# TK90X.net
KiCad netlist of a schematic drawn in EAGLE
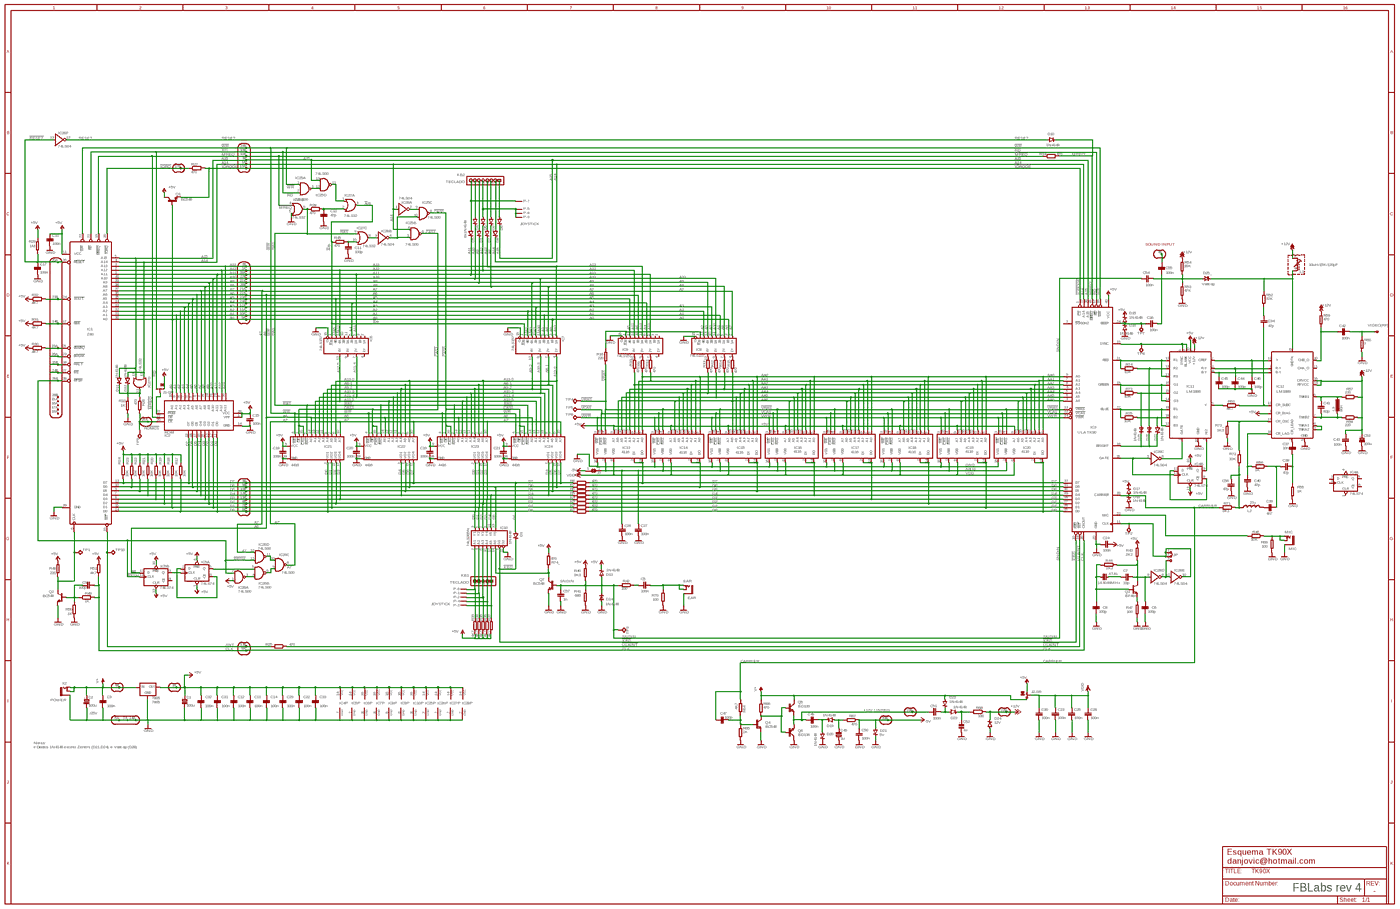
[diagram p0: schematic, sheet 1, overview]
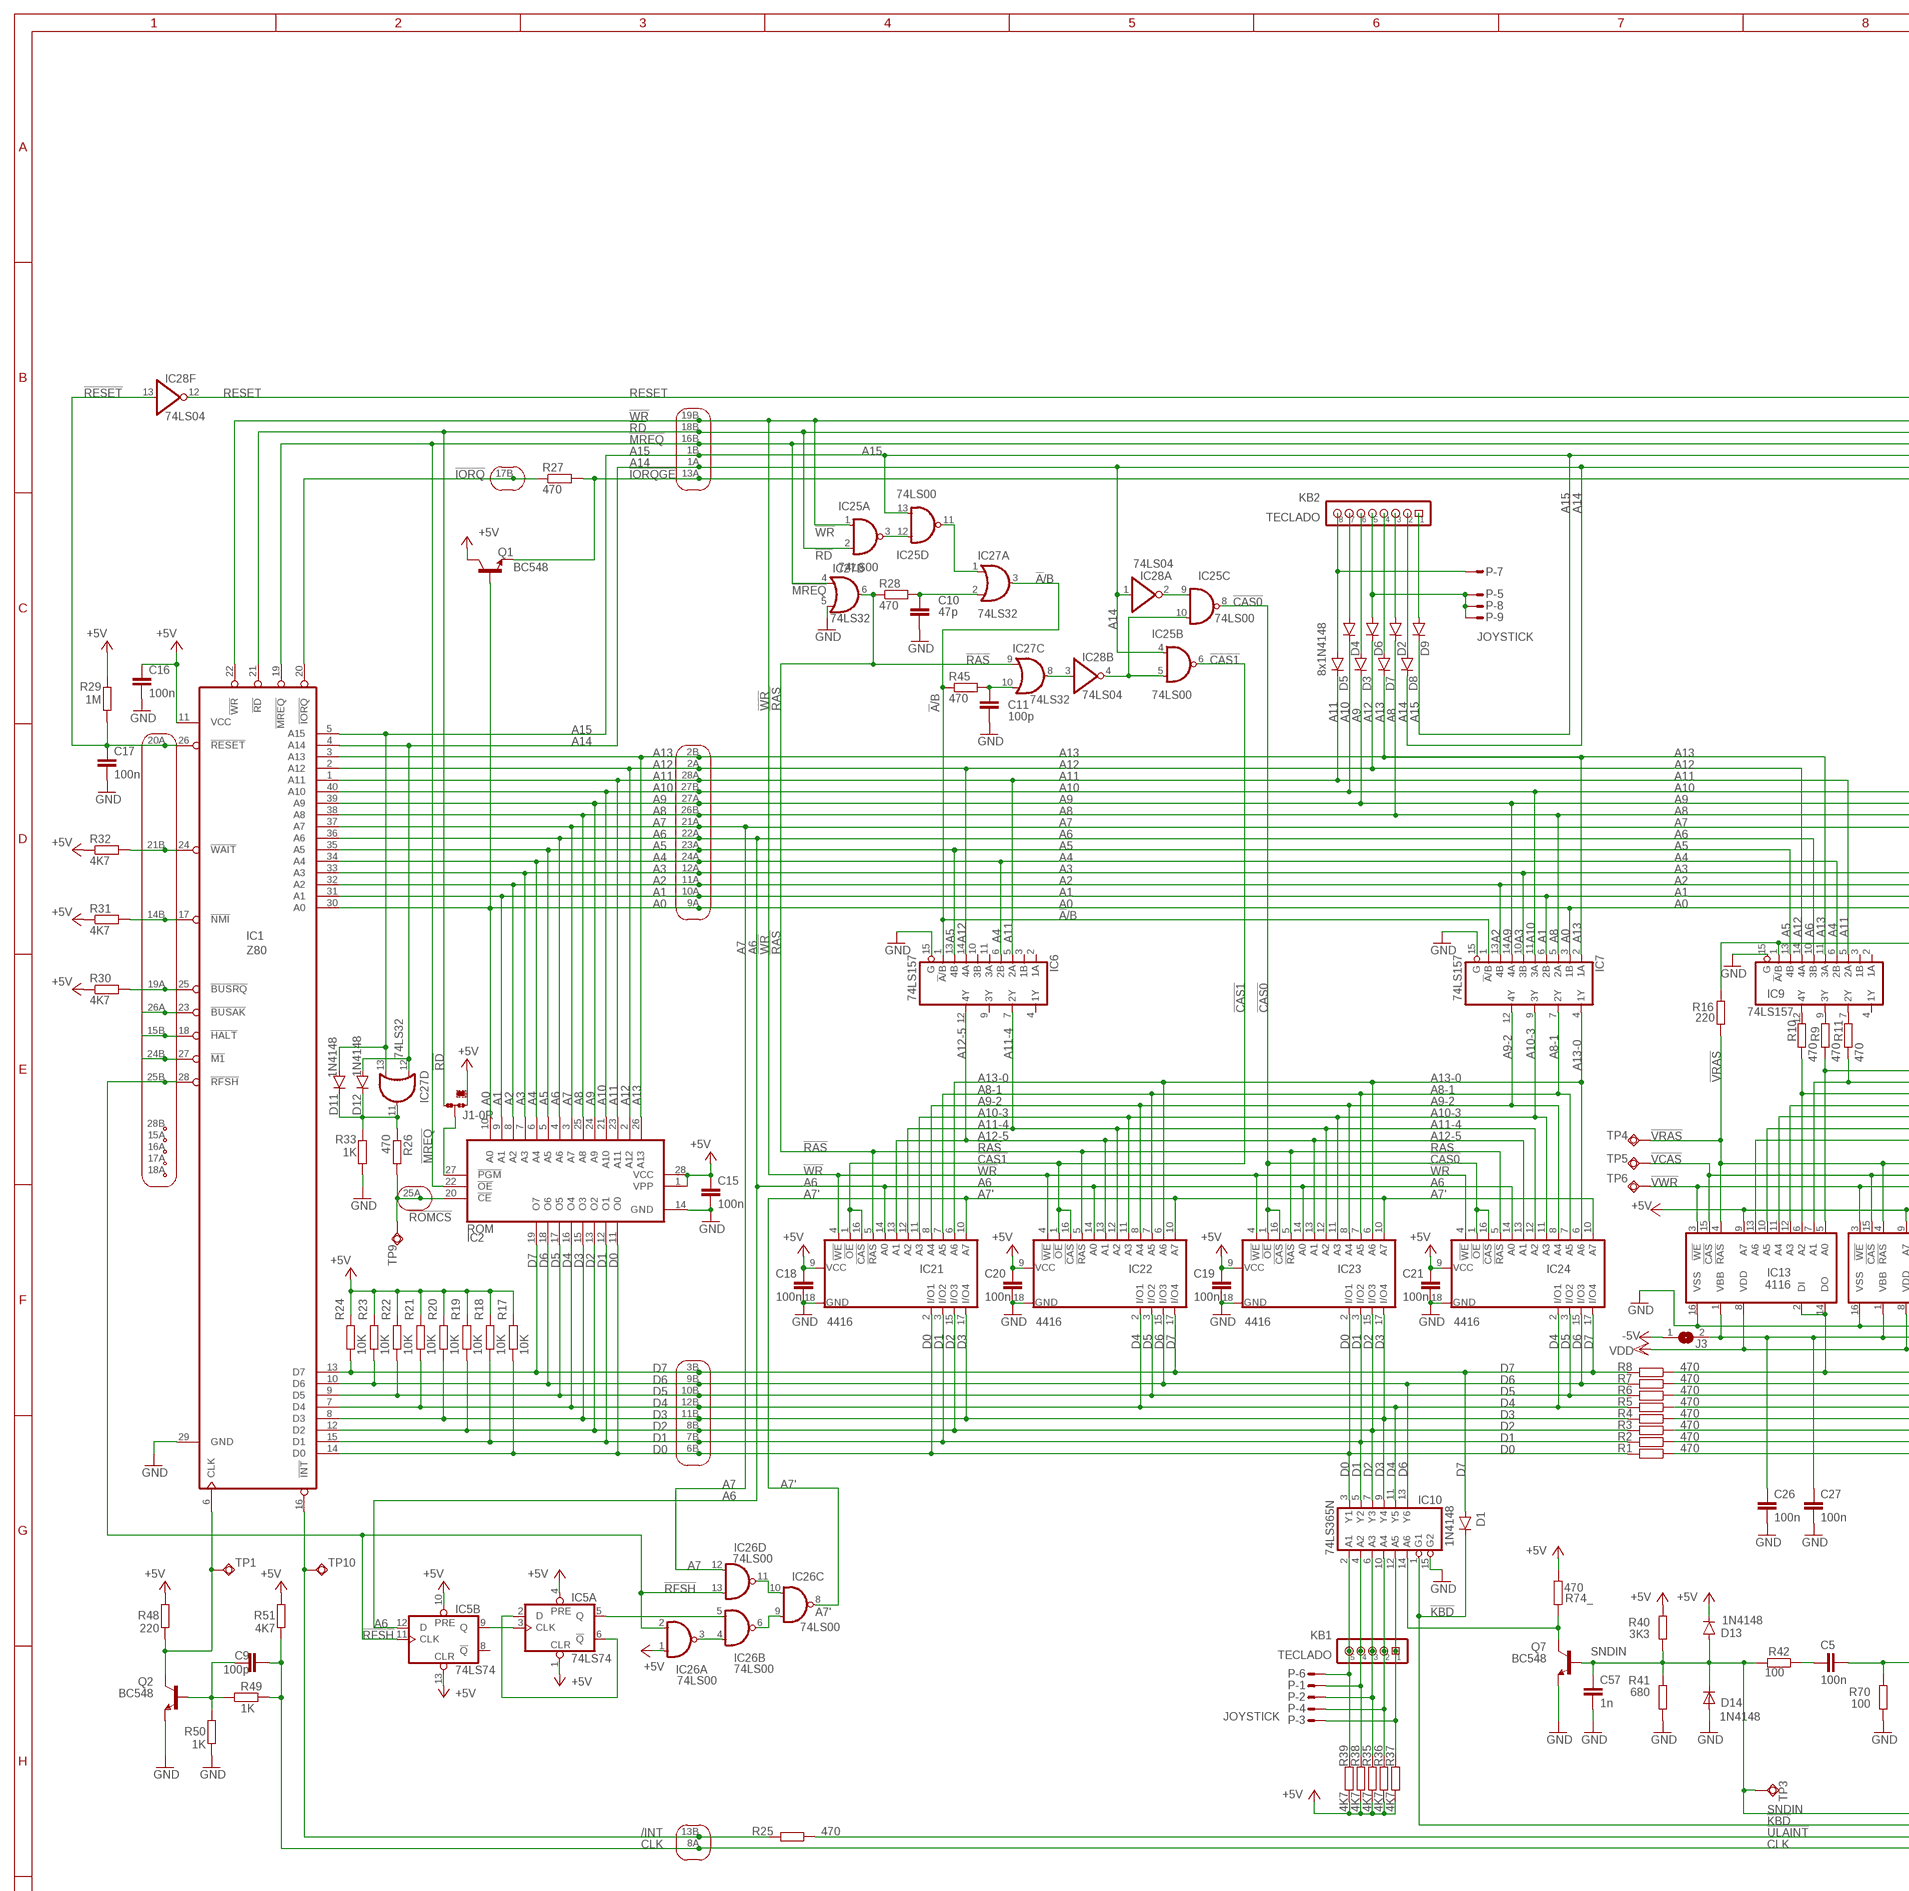
[diagram p1: schematic, sheet 1, part 1 of 4]
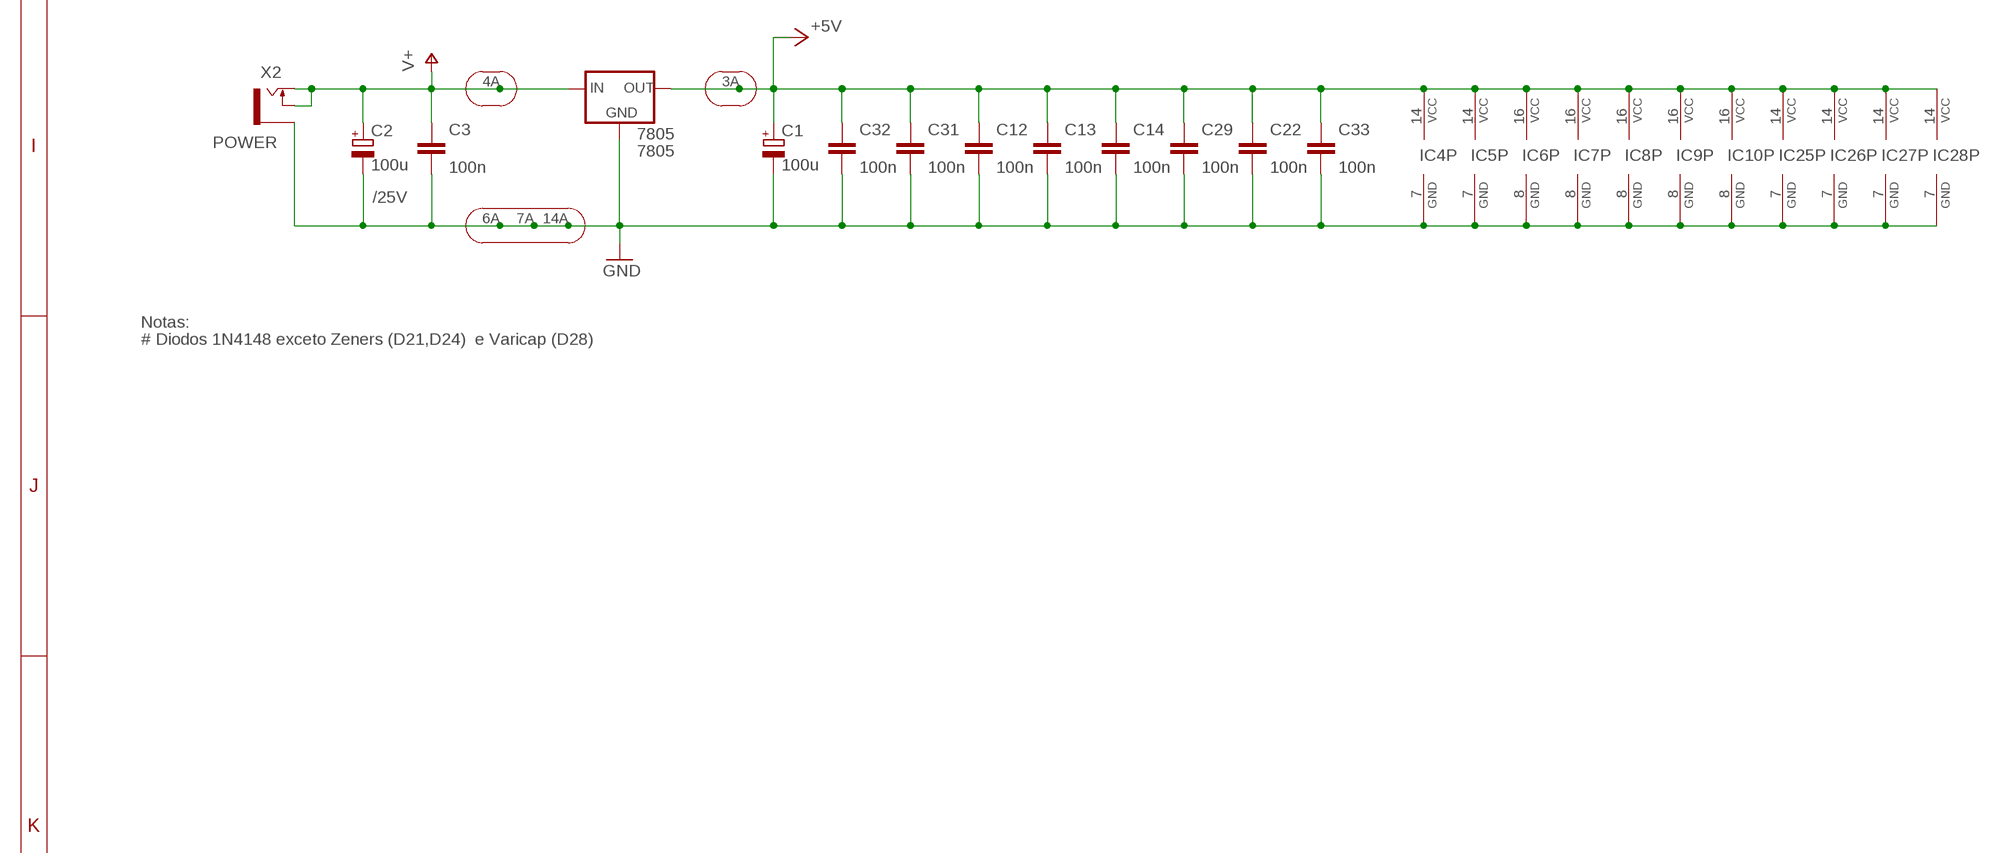
[diagram p2: schematic, sheet 1, part 2 of 4]
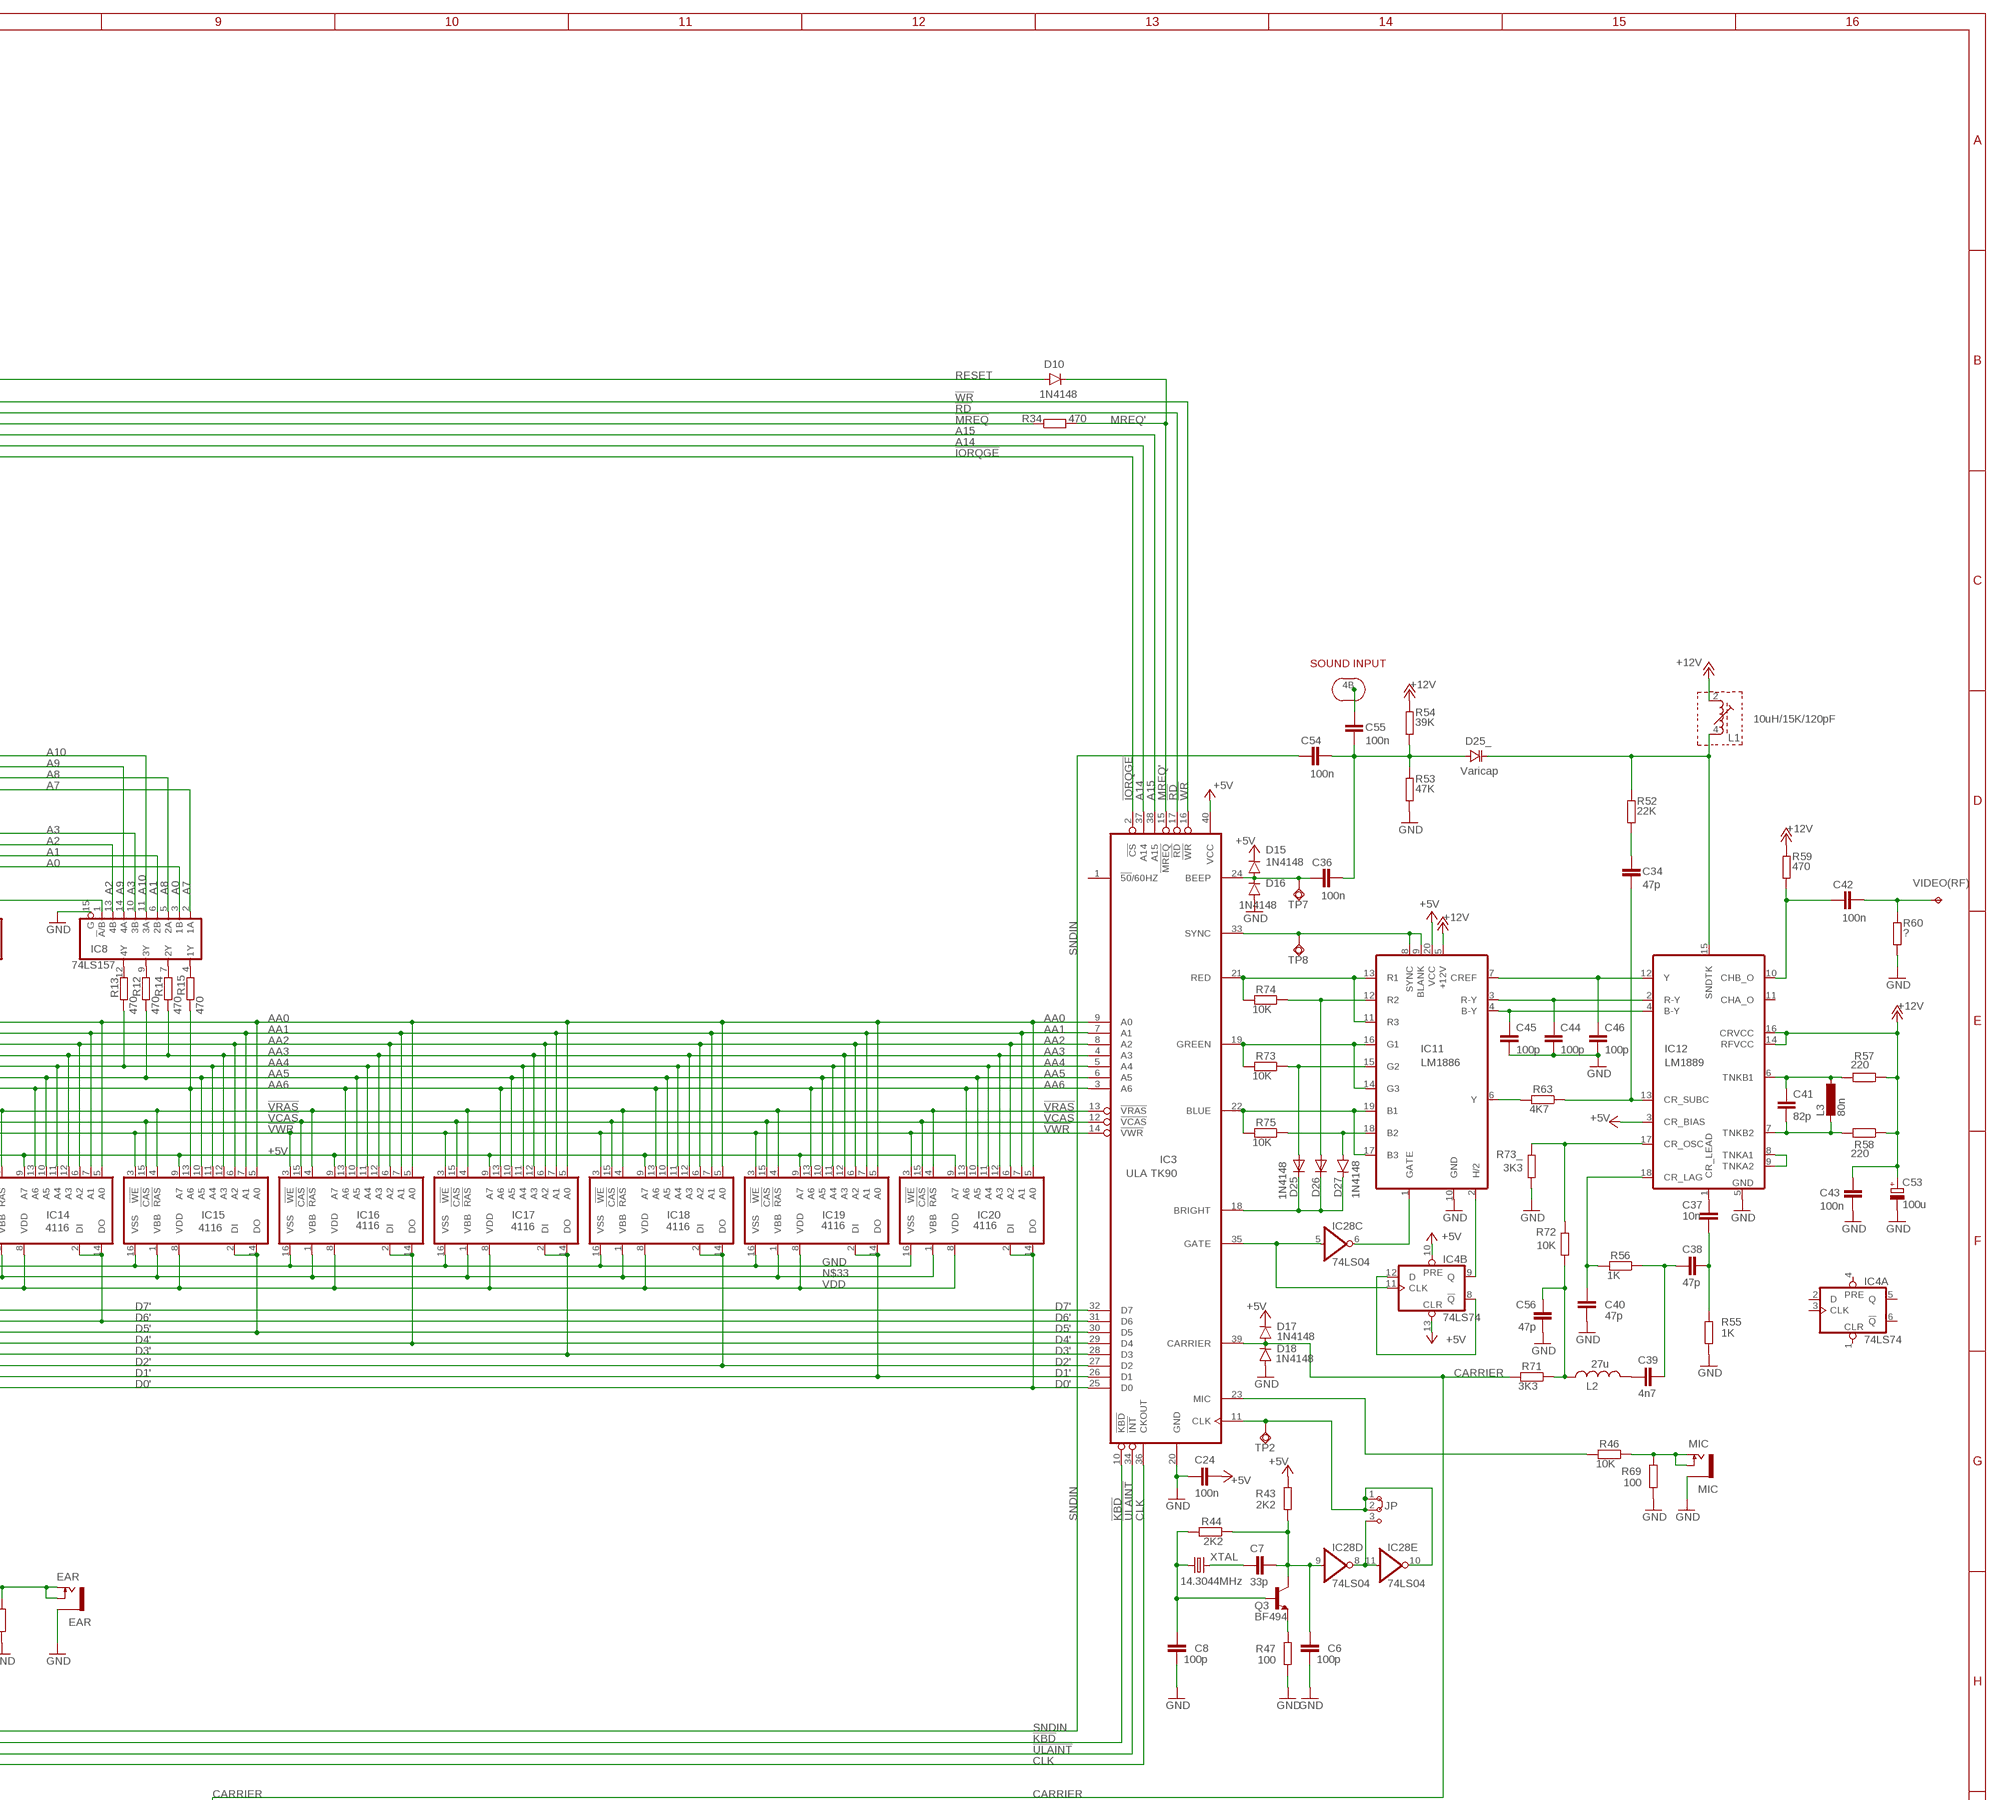
[diagram p3: schematic, sheet 1, part 3 of 4]
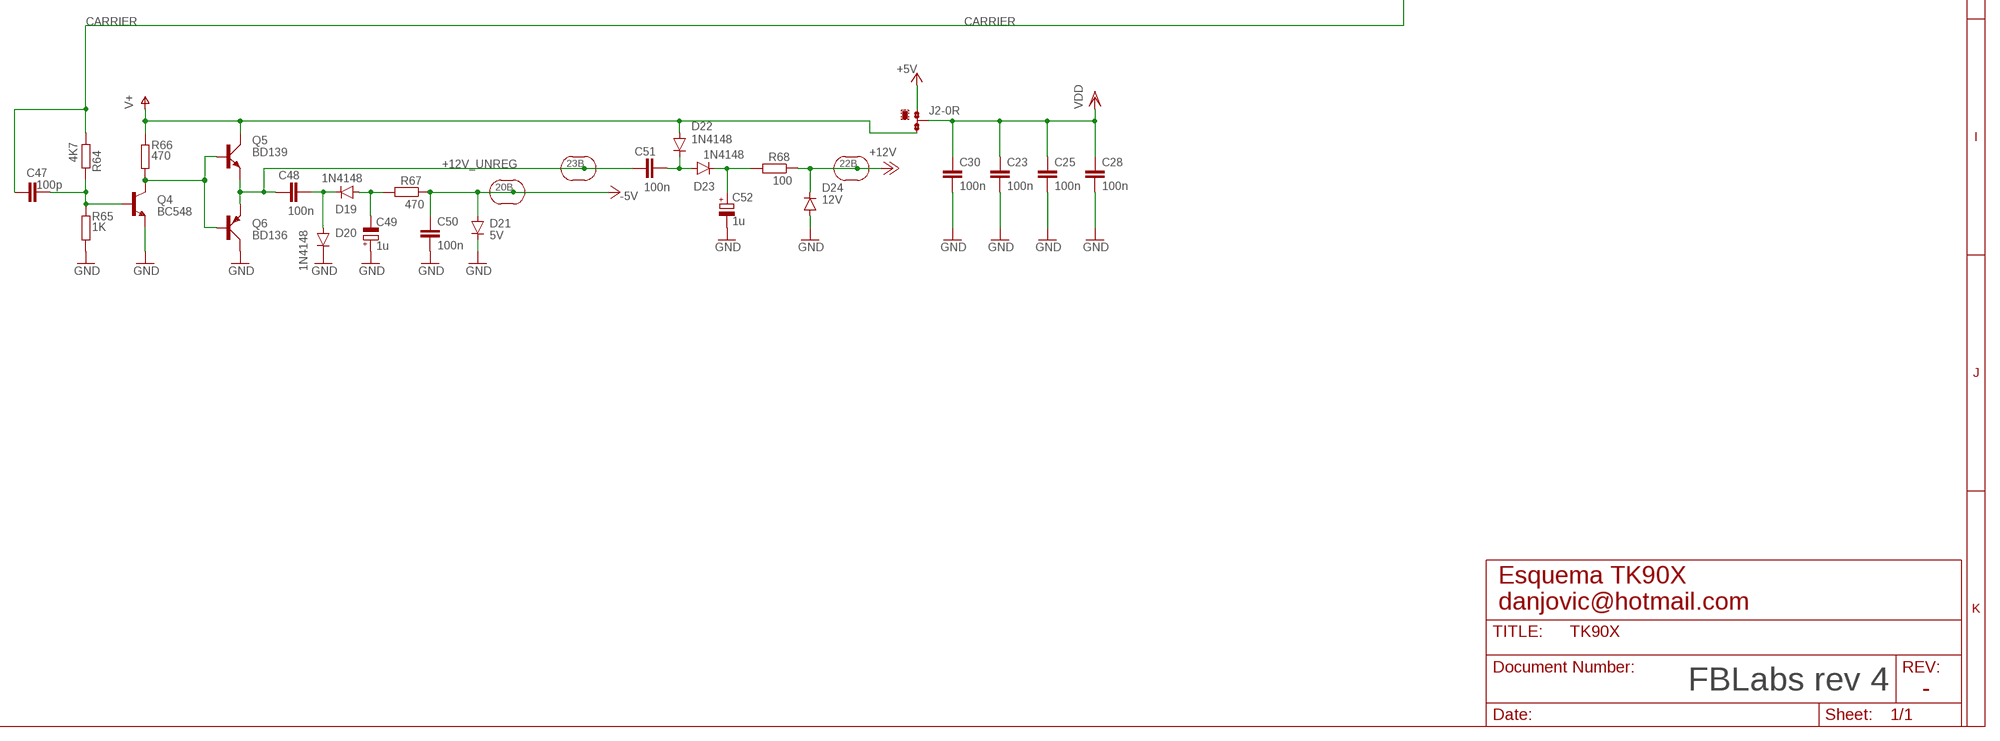
[diagram p4: schematic, sheet 1, part 4 of 4]

(export (version "E")
  (design (tool "Eeschema 10.0.6"))
  (components
    (comp (ref "7805")
      (value "7805")
      (footprint "eagle-import:78XXL")
      (libsource (lib "eagle-import") (part "78XXL"))
    )
    (comp (ref "C1")
      (value "100u")
      (footprint "eagle-import:E5-8,5")
      (libsource (lib "eagle-import") (part "CPOL-EUE5-8.5"))
    )
    (comp (ref "C2")
      (value "100u")
      (footprint "eagle-import:E5-8,5")
      (libsource (lib "eagle-import") (part "CPOL-EUE5-8.5"))
    )
    (comp (ref "C3")
      (value "100n")
      (footprint "eagle-import:C050-024X044")
      (libsource (lib "eagle-import") (part "C-EU050-024X044"))
    )
    (comp (ref "C5")
      (value "100n")
      (footprint "eagle-import:C050-024X044")
      (libsource (lib "eagle-import") (part "C-EU050-024X044"))
    )
    (comp (ref "C6")
      (value "100p")
      (footprint "eagle-import:C050-024X044")
      (libsource (lib "eagle-import") (part "C-EU050-024X044"))
    )
    (comp (ref "C7")
      (value "33p")
      (footprint "eagle-import:C050-024X044")
      (libsource (lib "eagle-import") (part "C-EU050-024X044"))
    )
    (comp (ref "C8")
      (value "100p")
      (footprint "eagle-import:C050-024X044")
      (libsource (lib "eagle-import") (part "C-EU050-024X044"))
    )
    (comp (ref "C9")
      (value "100p")
      (footprint "eagle-import:C050-024X044")
      (libsource (lib "eagle-import") (part "C-EU050-024X044"))
    )
    (comp (ref "C10")
      (value "47p")
      (footprint "eagle-import:C050-024X044")
      (libsource (lib "eagle-import") (part "C-EU050-024X044"))
    )
    (comp (ref "C11")
      (value "100p")
      (footprint "eagle-import:C050-024X044")
      (libsource (lib "eagle-import") (part "C-EU050-024X044"))
    )
    (comp (ref "C12")
      (value "100n")
      (footprint "eagle-import:C050-024X044")
      (libsource (lib "eagle-import") (part "C-EU050-024X044"))
    )
    (comp (ref "C13")
      (value "100n")
      (footprint "eagle-import:C050-024X044")
      (libsource (lib "eagle-import") (part "C-EU050-024X044"))
    )
    (comp (ref "C14")
      (value "100n")
      (footprint "eagle-import:C050-024X044")
      (libsource (lib "eagle-import") (part "C-EU050-024X044"))
    )
    (comp (ref "C15")
      (value "100n")
      (footprint "eagle-import:C050-024X044")
      (libsource (lib "eagle-import") (part "C-EU050-024X044"))
    )
    (comp (ref "C16")
      (value "100n")
      (footprint "eagle-import:C050-024X044")
      (libsource (lib "eagle-import") (part "C-EU050-024X044"))
    )
    (comp (ref "C17")
      (value "100n")
      (footprint "eagle-import:C050-024X044")
      (libsource (lib "eagle-import") (part "C-EU050-024X044"))
    )
    (comp (ref "C18")
      (value "100n")
      (footprint "eagle-import:C050-024X044")
      (libsource (lib "eagle-import") (part "C-EU050-024X044"))
    )
    (comp (ref "C19")
      (value "100n")
      (footprint "eagle-import:C050-024X044")
      (libsource (lib "eagle-import") (part "C-EU050-024X044"))
    )
    (comp (ref "C20")
      (value "100n")
      (footprint "eagle-import:C050-024X044")
      (libsource (lib "eagle-import") (part "C-EU050-024X044"))
    )
    (comp (ref "C21")
      (value "100n")
      (footprint "eagle-import:C050-024X044")
      (libsource (lib "eagle-import") (part "C-EU050-024X044"))
    )
    (comp (ref "C22")
      (value "100n")
      (footprint "eagle-import:C050-024X044")
      (libsource (lib "eagle-import") (part "C-EU050-024X044"))
    )
    (comp (ref "C23")
      (value "100n")
      (footprint "eagle-import:C050-024X044")
      (libsource (lib "eagle-import") (part "C-EU050-024X044"))
    )
    (comp (ref "C24")
      (value "100n")
      (footprint "eagle-import:C050-024X044")
      (libsource (lib "eagle-import") (part "C-EU050-024X044"))
    )
    (comp (ref "C25")
      (value "100n")
      (footprint "eagle-import:C050-024X044")
      (libsource (lib "eagle-import") (part "C-EU050-024X044"))
    )
    (comp (ref "C26")
      (value "100n")
      (footprint "eagle-import:C050-024X044")
      (libsource (lib "eagle-import") (part "C-EU050-024X044"))
    )
    (comp (ref "C27")
      (value "100n")
      (footprint "eagle-import:C050-024X044")
      (libsource (lib "eagle-import") (part "C-EU050-024X044"))
    )
    (comp (ref "C28")
      (value "100n")
      (footprint "eagle-import:C050-024X044")
      (libsource (lib "eagle-import") (part "C-EU050-024X044"))
    )
    (comp (ref "C29")
      (value "100n")
      (footprint "eagle-import:C050-024X044")
      (libsource (lib "eagle-import") (part "C-EU050-024X044"))
    )
    (comp (ref "C30")
      (value "100n")
      (footprint "eagle-import:C050-024X044")
      (libsource (lib "eagle-import") (part "C-EU050-024X044"))
    )
    (comp (ref "C31")
      (value "100n")
      (footprint "eagle-import:C050-024X044")
      (libsource (lib "eagle-import") (part "C-EU050-024X044"))
    )
    (comp (ref "C32")
      (value "100n")
      (footprint "eagle-import:C050-024X044")
      (libsource (lib "eagle-import") (part "C-EU050-024X044"))
    )
    (comp (ref "C33")
      (value "100n")
      (footprint "eagle-import:C050-024X044")
      (libsource (lib "eagle-import") (part "C-EU050-024X044"))
    )
    (comp (ref "C34")
      (value "47p")
      (footprint "eagle-import:C050-024X044")
      (libsource (lib "eagle-import") (part "C-EU050-024X044"))
    )
    (comp (ref "C36")
      (value "100n")
      (footprint "eagle-import:C050-024X044")
      (libsource (lib "eagle-import") (part "C-EU050-024X044"))
    )
    (comp (ref "C37")
      (value "10n")
      (footprint "eagle-import:C050-024X044")
      (libsource (lib "eagle-import") (part "C-EU050-024X044"))
    )
    (comp (ref "C38")
      (value "47p")
      (footprint "eagle-import:C050-024X044")
      (libsource (lib "eagle-import") (part "C-EU050-024X044"))
    )
    (comp (ref "C39")
      (value "4n7")
      (footprint "eagle-import:C050-024X044")
      (libsource (lib "eagle-import") (part "C-EU050-024X044"))
    )
    (comp (ref "C40")
      (value "47p")
      (footprint "eagle-import:C050-024X044")
      (libsource (lib "eagle-import") (part "C-EU050-024X044"))
    )
    (comp (ref "C41")
      (value "82p")
      (footprint "eagle-import:C050-024X044")
      (libsource (lib "eagle-import") (part "C-EU050-024X044"))
    )
    (comp (ref "C42")
      (value "100n")
      (footprint "eagle-import:C050-024X044")
      (libsource (lib "eagle-import") (part "C-EU050-024X044"))
    )
    (comp (ref "C43")
      (value "100n")
      (footprint "eagle-import:C050-024X044")
      (libsource (lib "eagle-import") (part "C-EU050-024X044"))
    )
    (comp (ref "C44")
      (value "100p")
      (footprint "eagle-import:C050-024X044")
      (libsource (lib "eagle-import") (part "C-EU050-024X044"))
    )
    (comp (ref "C45")
      (value "100p")
      (footprint "eagle-import:C050-024X044")
      (libsource (lib "eagle-import") (part "C-EU050-024X044"))
    )
    (comp (ref "C46")
      (value "100p")
      (footprint "eagle-import:C050-024X044")
      (libsource (lib "eagle-import") (part "C-EU050-024X044"))
    )
    (comp (ref "C47")
      (value "100p")
      (footprint "eagle-import:C050-024X044")
      (libsource (lib "eagle-import") (part "C-EU050-024X044"))
    )
    (comp (ref "C48")
      (value "100n")
      (footprint "eagle-import:C050-024X044")
      (libsource (lib "eagle-import") (part "C-EU050-024X044"))
    )
    (comp (ref "C49")
      (value "1u")
      (footprint "eagle-import:E2-4")
      (libsource (lib "eagle-import") (part "CPOL-EUE2-4"))
    )
    (comp (ref "C50")
      (value "100n")
      (footprint "eagle-import:C050-024X044")
      (libsource (lib "eagle-import") (part "C-EU050-024X044"))
    )
    (comp (ref "C51")
      (value "100n")
      (footprint "eagle-import:C050-024X044")
      (libsource (lib "eagle-import") (part "C-EU050-024X044"))
    )
    (comp (ref "C52")
      (value "1u")
      (footprint "eagle-import:E2-5")
      (libsource (lib "eagle-import") (part "CPOL-EUE2-5"))
    )
    (comp (ref "C53")
      (value "100u")
      (footprint "eagle-import:E5-4")
      (libsource (lib "eagle-import") (part "CPOL-EUE5-4"))
    )
    (comp (ref "C54")
      (value "100n")
      (footprint "eagle-import:C050-024X044")
      (libsource (lib "eagle-import") (part "C-EU050-024X044"))
    )
    (comp (ref "C55")
      (value "100n")
      (footprint "eagle-import:C050-024X044")
      (libsource (lib "eagle-import") (part "C-EU050-024X044"))
    )
    (comp (ref "C56")
      (value "47p")
      (footprint "eagle-import:C050-024X044")
      (libsource (lib "eagle-import") (part "C-EU050-024X044"))
    )
    (comp (ref "C57")
      (value "1n")
      (footprint "eagle-import:C050-024X044")
      (libsource (lib "eagle-import") (part "C-EU050-024X044"))
    )
    (comp (ref "D1")
      (value "1N4148")
      (footprint "eagle-import:DO35-12")
      (libsource (lib "eagle-import") (part "DDO35-12"))
    )
    (comp (ref "D2")
      (value "1N4148")
      (footprint "eagle-import:DO35-12")
      (libsource (lib "eagle-import") (part "DDO35-12"))
    )
    (comp (ref "D3")
      (value "1N4148")
      (footprint "eagle-import:DO35-12")
      (libsource (lib "eagle-import") (part "DDO35-12"))
    )
    (comp (ref "D4")
      (value "1N4148")
      (footprint "eagle-import:DO35-12")
      (libsource (lib "eagle-import") (part "DDO35-12"))
    )
    (comp (ref "D5")
      (value "1N4148")
      (footprint "eagle-import:DO35-12")
      (libsource (lib "eagle-import") (part "DDO35-12"))
    )
    (comp (ref "D6")
      (value "1N4148")
      (footprint "eagle-import:DO35-12")
      (libsource (lib "eagle-import") (part "DDO35-12"))
    )
    (comp (ref "D7")
      (value "1N4148")
      (footprint "eagle-import:DO35-12")
      (libsource (lib "eagle-import") (part "DDO35-12"))
    )
    (comp (ref "D8")
      (value "1N4148")
      (footprint "eagle-import:DO35-12")
      (libsource (lib "eagle-import") (part "DDO35-12"))
    )
    (comp (ref "D9")
      (value "1N4148")
      (footprint "eagle-import:DO35-12")
      (libsource (lib "eagle-import") (part "DDO35-12"))
    )
    (comp (ref "D10")
      (value "1N4148")
      (footprint "eagle-import:DO35-12")
      (libsource (lib "eagle-import") (part "DDO35-12"))
    )
    (comp (ref "D11")
      (value "1N4148")
      (footprint "eagle-import:DO35-12")
      (libsource (lib "eagle-import") (part "DDO35-12"))
    )
    (comp (ref "D12")
      (value "1N4148")
      (footprint "eagle-import:DO35-12")
      (libsource (lib "eagle-import") (part "DDO35-12"))
    )
    (comp (ref "D13")
      (value "1N4148")
      (footprint "eagle-import:DO35-12")
      (libsource (lib "eagle-import") (part "DDO35-12"))
    )
    (comp (ref "D14")
      (value "1N4148")
      (footprint "eagle-import:D-5")
      (libsource (lib "eagle-import") (part "DIODE-D-5"))
    )
    (comp (ref "D15")
      (value "1N4148")
      (footprint "eagle-import:DO35-12")
      (libsource (lib "eagle-import") (part "DDO35-12"))
    )
    (comp (ref "D16")
      (value "1N4148")
      (footprint "eagle-import:DO35-12")
      (libsource (lib "eagle-import") (part "DDO35-12"))
    )
    (comp (ref "D17")
      (value "1N4148")
      (footprint "eagle-import:DO35-12")
      (libsource (lib "eagle-import") (part "DDO35-12"))
    )
    (comp (ref "D18")
      (value "1N4148")
      (footprint "eagle-import:DO35-12")
      (libsource (lib "eagle-import") (part "DDO35-12"))
    )
    (comp (ref "D19")
      (value "1N4148")
      (footprint "eagle-import:DO35-12")
      (libsource (lib "eagle-import") (part "DDO35-12"))
    )
    (comp (ref "D20")
      (value "1N4148")
      (footprint "eagle-import:DO35-12")
      (libsource (lib "eagle-import") (part "DDO35-12"))
    )
    (comp (ref "D21")
      (value "5V")
      (footprint "eagle-import:DO35-12")
      (libsource (lib "eagle-import") (part "DDO35-12"))
    )
    (comp (ref "D22")
      (value "1N4148")
      (footprint "eagle-import:DO35-12")
      (libsource (lib "eagle-import") (part "DDO35-12"))
    )
    (comp (ref "D23")
      (value "1N4148")
      (footprint "eagle-import:DO35-12")
      (libsource (lib "eagle-import") (part "DDO35-12"))
    )
    (comp (ref "D24")
      (value "12V")
      (footprint "eagle-import:DO35-12")
      (libsource (lib "eagle-import") (part "DDO35-12"))
    )
    (comp (ref "D25")
      (value "1N4148")
      (footprint "eagle-import:D-5")
      (libsource (lib "eagle-import") (part "DIODE-D-5"))
    )
    (comp (ref "D25_")
      (value "Varicap")
      (footprint "eagle-import:D200")
      (libsource (lib "eagle-import") (part "VARICAP-200"))
    )
    (comp (ref "D26")
      (value "1N4148")
      (footprint "eagle-import:D-5")
      (libsource (lib "eagle-import") (part "DIODE-D-5"))
    )
    (comp (ref "D27")
      (value "1N4148")
      (footprint "eagle-import:DO35-12")
      (libsource (lib "eagle-import") (part "DDO35-12"))
    )
    (comp (ref "EAR")
      (value "EAR")
      (footprint "eagle-import:MONO")
      (libsource (lib "eagle-import") (part "JACK?-MONO"))
    )
    (comp (ref "IC1")
      (value "Z80")
      (footprint "eagle-import:DIL40")
      (libsource (lib "eagle-import") (part "Z80CPU"))
    )
    (comp (ref "IC2")
      (value "ROM")
      (footprint "eagle-import:DIL28")
      (libsource (lib "eagle-import") (part "25128"))
    )
    (comp (ref "IC3")
      (value "ULA TK90")
      (footprint "eagle-import:DIL40")
      (libsource (lib "eagle-import") (part "ULA-TK90"))
    )
    (comp (ref "IC4")
      (value "74LS74")
      (footprint "eagle-import:DIL14")
      (libsource (lib "eagle-import") (part "7474NLS"))
    )
    (comp (ref "IC5")
      (value "74LS74")
      (footprint "eagle-import:DIL14")
      (libsource (lib "eagle-import") (part "7474NLS"))
    )
    (comp (ref "IC6")
      (value "74LS157")
      (footprint "eagle-import:DIL16")
      (libsource (lib "eagle-import") (part "74157NS"))
    )
    (comp (ref "IC7")
      (value "74LS157")
      (footprint "eagle-import:DIL16")
      (libsource (lib "eagle-import") (part "74157NS"))
    )
    (comp (ref "IC8")
      (value "74LS157")
      (footprint "eagle-import:DIL16")
      (libsource (lib "eagle-import") (part "74157NS"))
    )
    (comp (ref "IC9")
      (value "74LS157")
      (footprint "eagle-import:DIL16")
      (libsource (lib "eagle-import") (part "74157NS"))
    )
    (comp (ref "IC10")
      (value "74LS365N")
      (footprint "eagle-import:DIL16")
      (libsource (lib "eagle-import") (part "74365NLS"))
    )
    (comp (ref "IC11")
      (value "LM1886")
      (footprint "eagle-import:DIL20")
      (libsource (lib "eagle-import") (part "LM1886N"))
    )
    (comp (ref "IC12")
      (value "LM1889")
      (footprint "eagle-import:DIL18")
      (libsource (lib "eagle-import") (part "LM1889"))
    )
    (comp (ref "IC13")
      (value "4116")
      (footprint "eagle-import:DIL16")
      (libsource (lib "eagle-import") (part "MK4516"))
    )
    (comp (ref "IC14")
      (value "4116")
      (footprint "eagle-import:DIL16")
      (libsource (lib "eagle-import") (part "MK4516"))
    )
    (comp (ref "IC15")
      (value "4116")
      (footprint "eagle-import:DIL16")
      (libsource (lib "eagle-import") (part "MK4516"))
    )
    (comp (ref "IC16")
      (value "4116")
      (footprint "eagle-import:DIL16")
      (libsource (lib "eagle-import") (part "MK4516"))
    )
    (comp (ref "IC17")
      (value "4116")
      (footprint "eagle-import:DIL16")
      (libsource (lib "eagle-import") (part "MK4516"))
    )
    (comp (ref "IC18")
      (value "4116")
      (footprint "eagle-import:DIL16")
      (libsource (lib "eagle-import") (part "MK4516"))
    )
    (comp (ref "IC19")
      (value "4116")
      (footprint "eagle-import:DIL16")
      (libsource (lib "eagle-import") (part "MK4516"))
    )
    (comp (ref "IC20")
      (value "4116")
      (footprint "eagle-import:DIL16")
      (libsource (lib "eagle-import") (part "MK4516"))
    )
    (comp (ref "IC21")
      (value "4416")
      (footprint "eagle-import:DIL18")
      (libsource (lib "eagle-import") (part "4416"))
    )
    (comp (ref "IC22")
      (value "4416")
      (footprint "eagle-import:DIL18")
      (libsource (lib "eagle-import") (part "4416"))
    )
    (comp (ref "IC23")
      (value "4416")
      (footprint "eagle-import:DIL18")
      (libsource (lib "eagle-import") (part "4416"))
    )
    (comp (ref "IC24")
      (value "4416")
      (footprint "eagle-import:DIL18")
      (libsource (lib "eagle-import") (part "4416"))
    )
    (comp (ref "IC25")
      (value "74LS00")
      (footprint "eagle-import:DIL14")
      (libsource (lib "eagle-import") (part "7400NLS"))
    )
    (comp (ref "IC26")
      (value "74LS00")
      (footprint "eagle-import:DIL14")
      (libsource (lib "eagle-import") (part "7400NLS"))
    )
    (comp (ref "IC27")
      (value "74LS32")
      (footprint "eagle-import:DIL14")
      (libsource (lib "eagle-import") (part "7432NLS"))
    )
    (comp (ref "IC28")
      (value "74LS04")
      (footprint "eagle-import:DIL14")
      (libsource (lib "eagle-import") (part "7404NLS"))
    )
    (comp (ref "J1")
      (value "0R-JUMPB")
      (footprint "eagle-import:B0R-JMP")
      (libsource (lib "eagle-import") (part "0R-JUMPB"))
    )
    (comp (ref "J2")
      (value "0R-JUMPB")
      (footprint "eagle-import:B0R-JMP")
      (libsource (lib "eagle-import") (part "0R-JUMPB"))
    )
    (comp (ref "J3") (value "SJ") (footprint "eagle-import:SJ") (libsource (lib "eagle-import") (part "SJ")))
    (comp (ref "JP")
      (value "J2X1MM")
      (footprint "eagle-import:03C")
      (libsource (lib "eagle-import") (part "J2X1MM"))
    )
    (comp (ref "KB1")
      (value "TECLADO")
      (footprint "eagle-import:FE05-1")
      (libsource (lib "eagle-import") (part "CON-TECL-5"))
    )
    (comp (ref "KB2")
      (value "TECLADO")
      (footprint "eagle-import:FE08")
      (libsource (lib "eagle-import") (part "CON-TECL-8"))
    )
    (comp (ref "L1")
      (value "10uH/15K/120pF")
      (footprint "eagle-import:COIL")
      (libsource (lib "eagle-import") (part "COIL"))
    )
    (comp (ref "L2")
      (value "27u")
      (footprint "eagle-import:0207_7")
      (libsource (lib "eagle-import") (part "L-US0207/7"))
    )
    (comp (ref "L3")
      (value "80n")
      (footprint "eagle-import:0204_5")
      (libsource (lib "eagle-import") (part "L-EU0204/5"))
    )
    (comp (ref "MIC")
      (value "MIC")
      (footprint "eagle-import:MONO")
      (libsource (lib "eagle-import") (part "JACK?-MONO"))
    )
    (comp (ref "P")
      (value "JOYSTICK")
      (footprint "eagle-import:177-009-MALE")
      (libsource (lib "eagle-import") (part "M09?S.590"))
    )
    (comp (ref "Q1")
      (value "BC548")
      (footprint "eagle-import:TO92L")
      (libsource (lib "eagle-import") (part "-NPN-TO92L"))
    )
    (comp (ref "Q2")
      (value "BC548")
      (footprint "eagle-import:TO92L")
      (libsource (lib "eagle-import") (part "-NPN-TO92L"))
    )
    (comp (ref "Q3")
      (value "BF494")
      (footprint "eagle-import:TO92-CEB")
      (libsource (lib "eagle-import") (part "BF494"))
    )
    (comp (ref "Q4")
      (value "BC548")
      (footprint "eagle-import:TO92L")
      (libsource (lib "eagle-import") (part "-NPN-TO92L"))
    )
    (comp (ref "Q5")
      (value "BD139")
      (footprint "eagle-import:TO126AV")
      (libsource (lib "eagle-import") (part "BD139"))
    )
    (comp (ref "Q6")
      (value "BD136")
      (footprint "eagle-import:TO126AV")
      (libsource (lib "eagle-import") (part "BD140"))
    )
    (comp (ref "Q7")
      (value "BC548")
      (footprint "eagle-import:TO92L")
      (libsource (lib "eagle-import") (part "-NPN-TO92L"))
    )
    (comp (ref "R1")
      (value "470")
      (footprint "eagle-import:0207_12")
      (libsource (lib "eagle-import") (part "R-EU_0207/12"))
    )
    (comp (ref "R2")
      (value "470")
      (footprint "eagle-import:0207_12")
      (libsource (lib "eagle-import") (part "R-EU_0207/12"))
    )
    (comp (ref "R3")
      (value "470")
      (footprint "eagle-import:0207_12")
      (libsource (lib "eagle-import") (part "R-EU_0207/12"))
    )
    (comp (ref "R4")
      (value "470")
      (footprint "eagle-import:0207_12")
      (libsource (lib "eagle-import") (part "R-EU_0207/12"))
    )
    (comp (ref "R5")
      (value "470")
      (footprint "eagle-import:0207_12")
      (libsource (lib "eagle-import") (part "R-EU_0207/12"))
    )
    (comp (ref "R6")
      (value "470")
      (footprint "eagle-import:0207_12")
      (libsource (lib "eagle-import") (part "R-EU_0207/12"))
    )
    (comp (ref "R7")
      (value "470")
      (footprint "eagle-import:0207_12")
      (libsource (lib "eagle-import") (part "R-EU_0207/12"))
    )
    (comp (ref "R8")
      (value "470")
      (footprint "eagle-import:0207_12")
      (libsource (lib "eagle-import") (part "R-EU_0207/12"))
    )
    (comp (ref "R9")
      (value "470")
      (footprint "eagle-import:0207_12")
      (libsource (lib "eagle-import") (part "R-EU_0207/12"))
    )
    (comp (ref "R10")
      (value "470")
      (footprint "eagle-import:0207_12")
      (libsource (lib "eagle-import") (part "R-EU_0207/12"))
    )
    (comp (ref "R11")
      (value "470")
      (footprint "eagle-import:0207_12")
      (libsource (lib "eagle-import") (part "R-EU_0207/12"))
    )
    (comp (ref "R12")
      (value "470")
      (footprint "eagle-import:0207_12")
      (libsource (lib "eagle-import") (part "R-EU_0207/12"))
    )
    (comp (ref "R13")
      (value "470")
      (footprint "eagle-import:0207_12")
      (libsource (lib "eagle-import") (part "R-EU_0207/12"))
    )
    (comp (ref "R14")
      (value "470")
      (footprint "eagle-import:0207_12")
      (libsource (lib "eagle-import") (part "R-EU_0207/12"))
    )
    (comp (ref "R15")
      (value "470")
      (footprint "eagle-import:0207_12")
      (libsource (lib "eagle-import") (part "R-EU_0207/12"))
    )
    (comp (ref "R16")
      (value "220")
      (footprint "eagle-import:0207_12")
      (libsource (lib "eagle-import") (part "R-EU_0207/12"))
    )
    (comp (ref "R17")
      (value "10K")
      (footprint "eagle-import:0207_12")
      (libsource (lib "eagle-import") (part "R-EU_0207/12"))
    )
    (comp (ref "R18")
      (value "10K")
      (footprint "eagle-import:0207_12")
      (libsource (lib "eagle-import") (part "R-EU_0207/12"))
    )
    (comp (ref "R19")
      (value "10K")
      (footprint "eagle-import:0207_12")
      (libsource (lib "eagle-import") (part "R-EU_0207/12"))
    )
    (comp (ref "R20")
      (value "10K")
      (footprint "eagle-import:0207_12")
      (libsource (lib "eagle-import") (part "R-EU_0207/12"))
    )
    (comp (ref "R21")
      (value "10K")
      (footprint "eagle-import:0207_12")
      (libsource (lib "eagle-import") (part "R-EU_0207/12"))
    )
    (comp (ref "R22")
      (value "10K")
      (footprint "eagle-import:0207_12")
      (libsource (lib "eagle-import") (part "R-EU_0207/12"))
    )
    (comp (ref "R23")
      (value "10K")
      (footprint "eagle-import:0207_12")
      (libsource (lib "eagle-import") (part "R-EU_0207/12"))
    )
    (comp (ref "R24")
      (value "10K")
      (footprint "eagle-import:0207_12")
      (libsource (lib "eagle-import") (part "R-EU_0207/12"))
    )
    (comp (ref "R25")
      (value "470")
      (footprint "eagle-import:0207_12")
      (libsource (lib "eagle-import") (part "R-EU_0207/12"))
    )
    (comp (ref "R26")
      (value "470")
      (footprint "eagle-import:0207_12")
      (libsource (lib "eagle-import") (part "R-EU_0207/12"))
    )
    (comp (ref "R27")
      (value "470")
      (footprint "eagle-import:0207_12")
      (libsource (lib "eagle-import") (part "R-EU_0207/12"))
    )
    (comp (ref "R28")
      (value "470")
      (footprint "eagle-import:0207_12")
      (libsource (lib "eagle-import") (part "R-EU_0207/12"))
    )
    (comp (ref "R29")
      (value "1M")
      (footprint "eagle-import:0207_12")
      (libsource (lib "eagle-import") (part "R-EU_0207/12"))
    )
    (comp (ref "R30")
      (value "4K7")
      (footprint "eagle-import:0207_12")
      (libsource (lib "eagle-import") (part "R-EU_0207/12"))
    )
    (comp (ref "R31")
      (value "4K7")
      (footprint "eagle-import:0207_12")
      (libsource (lib "eagle-import") (part "R-EU_0207/12"))
    )
    (comp (ref "R32")
      (value "4K7")
      (footprint "eagle-import:0207_12")
      (libsource (lib "eagle-import") (part "R-EU_0207/12"))
    )
    (comp (ref "R33")
      (value "1K")
      (footprint "eagle-import:0207_12")
      (libsource (lib "eagle-import") (part "R-EU_0207/12"))
    )
    (comp (ref "R34")
      (value "470")
      (footprint "eagle-import:0207_12")
      (libsource (lib "eagle-import") (part "R-EU_0207/12"))
    )
    (comp (ref "R35")
      (value "4K7")
      (footprint "eagle-import:0207_12")
      (libsource (lib "eagle-import") (part "R-EU_0207/12"))
    )
    (comp (ref "R36")
      (value "4K7")
      (footprint "eagle-import:0207_12")
      (libsource (lib "eagle-import") (part "R-EU_0207/12"))
    )
    (comp (ref "R37")
      (value "4K7")
      (footprint "eagle-import:0207_12")
      (libsource (lib "eagle-import") (part "R-EU_0207/12"))
    )
    (comp (ref "R38")
      (value "4K7")
      (footprint "eagle-import:0207_12")
      (libsource (lib "eagle-import") (part "R-EU_0207/12"))
    )
    (comp (ref "R39")
      (value "4K7")
      (footprint "eagle-import:0207_12")
      (libsource (lib "eagle-import") (part "R-EU_0207/12"))
    )
    (comp (ref "R40")
      (value "3K3")
      (footprint "eagle-import:0207_12")
      (libsource (lib "eagle-import") (part "R-EU_0207/12"))
    )
    (comp (ref "R41")
      (value "680")
      (footprint "eagle-import:0207_5V")
      (libsource (lib "eagle-import") (part "R-EU_0207/5V"))
    )
    (comp (ref "R42")
      (value "100")
      (footprint "eagle-import:0207_5V")
      (libsource (lib "eagle-import") (part "R-EU_0207/5V"))
    )
    (comp (ref "R43")
      (value "2K2")
      (footprint "eagle-import:0207_12")
      (libsource (lib "eagle-import") (part "R-EU_0207/12"))
    )
    (comp (ref "R44")
      (value "2K2")
      (footprint "eagle-import:0207_12")
      (libsource (lib "eagle-import") (part "R-EU_0207/12"))
    )
    (comp (ref "R45")
      (value "470")
      (footprint "eagle-import:0207_12")
      (libsource (lib "eagle-import") (part "R-EU_0207/12"))
    )
    (comp (ref "R46")
      (value "10K")
      (footprint "eagle-import:0207_12")
      (libsource (lib "eagle-import") (part "R-EU_0207/12"))
    )
    (comp (ref "R47")
      (value "100")
      (footprint "eagle-import:0207_12")
      (libsource (lib "eagle-import") (part "R-EU_0207/12"))
    )
    (comp (ref "R48")
      (value "220")
      (footprint "eagle-import:0207_12")
      (libsource (lib "eagle-import") (part "R-EU_0207/12"))
    )
    (comp (ref "R49")
      (value "1K")
      (footprint "eagle-import:0207_12")
      (libsource (lib "eagle-import") (part "R-EU_0207/12"))
    )
    (comp (ref "R50")
      (value "1K")
      (footprint "eagle-import:0207_12")
      (libsource (lib "eagle-import") (part "R-EU_0207/12"))
    )
    (comp (ref "R51")
      (value "4K7")
      (footprint "eagle-import:0207_12")
      (libsource (lib "eagle-import") (part "R-EU_0207/12"))
    )
    (comp (ref "R52")
      (value "22K")
      (footprint "eagle-import:0207_5V")
      (libsource (lib "eagle-import") (part "R-EU_0207/5V"))
    )
    (comp (ref "R53")
      (value "47K")
      (footprint "eagle-import:0207_12")
      (libsource (lib "eagle-import") (part "R-EU_0207/12"))
    )
    (comp (ref "R54")
      (value "39K")
      (footprint "eagle-import:0207_12")
      (libsource (lib "eagle-import") (part "R-EU_0207/12"))
    )
    (comp (ref "R55")
      (value "1K")
      (footprint "eagle-import:0207_5V")
      (libsource (lib "eagle-import") (part "R-EU_0207/5V"))
    )
    (comp (ref "R56")
      (value "1K")
      (footprint "eagle-import:0207_5V")
      (libsource (lib "eagle-import") (part "R-EU_0207/5V"))
    )
    (comp (ref "R57")
      (value "220")
      (footprint "eagle-import:0207_5V")
      (libsource (lib "eagle-import") (part "R-EU_0207/5V"))
    )
    (comp (ref "R58")
      (value "220")
      (footprint "eagle-import:0207_5V")
      (libsource (lib "eagle-import") (part "R-EU_0207/5V"))
    )
    (comp (ref "R59")
      (value "470")
      (footprint "eagle-import:0207_5V")
      (libsource (lib "eagle-import") (part "R-EU_0207/5V"))
    )
    (comp (ref "R60")
      (value "?")
      (footprint "eagle-import:0207_5V")
      (libsource (lib "eagle-import") (part "R-EU_0207/5V"))
    )
    (comp (ref "R63")
      (value "4K7")
      (footprint "eagle-import:0207_12")
      (libsource (lib "eagle-import") (part "R-EU_0207/12"))
    )
    (comp (ref "R64")
      (value "4K7")
      (footprint "eagle-import:0207_12")
      (libsource (lib "eagle-import") (part "R-EU_0207/12"))
    )
    (comp (ref "R65")
      (value "1K")
      (footprint "eagle-import:0207_12")
      (libsource (lib "eagle-import") (part "R-EU_0207/12"))
    )
    (comp (ref "R66")
      (value "470")
      (footprint "eagle-import:0207_12")
      (libsource (lib "eagle-import") (part "R-EU_0207/12"))
    )
    (comp (ref "R67")
      (value "470")
      (footprint "eagle-import:0207_12")
      (libsource (lib "eagle-import") (part "R-EU_0207/12"))
    )
    (comp (ref "R68")
      (value "100")
      (footprint "eagle-import:0207_12")
      (libsource (lib "eagle-import") (part "R-EU_0207/12"))
    )
    (comp (ref "R69")
      (value "100")
      (footprint "eagle-import:0207_5V")
      (libsource (lib "eagle-import") (part "R-EU_0207/5V"))
    )
    (comp (ref "R70")
      (value "100")
      (footprint "eagle-import:0207_5V")
      (libsource (lib "eagle-import") (part "R-EU_0207/5V"))
    )
    (comp (ref "R71")
      (value "3K3")
      (footprint "eagle-import:0207_5V")
      (libsource (lib "eagle-import") (part "R-EU_0207/5V"))
    )
    (comp (ref "R72")
      (value "10K")
      (footprint "eagle-import:0207_5V")
      (libsource (lib "eagle-import") (part "R-EU_0207/5V"))
    )
    (comp (ref "R73")
      (value "10K")
      (footprint "eagle-import:0207_5V")
      (libsource (lib "eagle-import") (part "R-EU_0207/5V"))
    )
    (comp (ref "R73_")
      (value "3K3")
      (footprint "eagle-import:0207_12")
      (libsource (lib "eagle-import") (part "R-EU_0207/12"))
    )
    (comp (ref "R74")
      (value "10K")
      (footprint "eagle-import:0207_5V")
      (libsource (lib "eagle-import") (part "R-EU_0207/5V"))
    )
    (comp (ref "R74_")
      (value "470")
      (footprint "eagle-import:0207_12")
      (libsource (lib "eagle-import") (part "R-EU_0207/12"))
    )
    (comp (ref "R75")
      (value "10K")
      (footprint "eagle-import:0207_12")
      (libsource (lib "eagle-import") (part "R-EU_0207/12"))
    )
    (comp (ref "TP1")
      (value "TPSQPAD1-13")
      (footprint "eagle-import:P1-13")
      (libsource (lib "eagle-import") (part "TPSQPAD1-13"))
    )
    (comp (ref "TP2")
      (value "TPSQPAD1-13")
      (footprint "eagle-import:P1-13")
      (libsource (lib "eagle-import") (part "TPSQPAD1-13"))
    )
    (comp (ref "TP3")
      (value "TPSQPAD1-13")
      (footprint "eagle-import:P1-13")
      (libsource (lib "eagle-import") (part "TPSQPAD1-13"))
    )
    (comp (ref "TP4")
      (value "TPSQPAD1-13")
      (footprint "eagle-import:P1-13")
      (libsource (lib "eagle-import") (part "TPSQPAD1-13"))
    )
    (comp (ref "TP5")
      (value "TPSQPAD1-13")
      (footprint "eagle-import:P1-13")
      (libsource (lib "eagle-import") (part "TPSQPAD1-13"))
    )
    (comp (ref "TP6")
      (value "TPSQPAD1-13")
      (footprint "eagle-import:P1-13")
      (libsource (lib "eagle-import") (part "TPSQPAD1-13"))
    )
    (comp (ref "TP7")
      (value "TPSQPAD1-13")
      (footprint "eagle-import:P1-13")
      (libsource (lib "eagle-import") (part "TPSQPAD1-13"))
    )
    (comp (ref "TP8")
      (value "TPSQPAD1-13")
      (footprint "eagle-import:P1-13")
      (libsource (lib "eagle-import") (part "TPSQPAD1-13"))
    )
    (comp (ref "TP9")
      (value "TPSQPAD1-13")
      (footprint "eagle-import:P1-13")
      (libsource (lib "eagle-import") (part "TPSQPAD1-13"))
    )
    (comp (ref "TP10")
      (value "TPSQPAD1-13")
      (footprint "eagle-import:P1-13")
      (libsource (lib "eagle-import") (part "TPSQPAD1-13"))
    )
    (comp (ref "U$1")
      (value "TK90_EDGE")
      (footprint "eagle-import:TK-EDGE")
      (libsource (lib "eagle-import") (part "TK90_EDGE"))
    )
    (comp (ref "VIDEO(RF)")
      (value "RF")
      (footprint "eagle-import:P1-13")
      (libsource (lib "eagle-import") (part "TPPAD1-13"))
    )
    (comp (ref "X2")
      (value "POWER")
      (footprint "eagle-import:MONO")
      (libsource (lib "eagle-import") (part "JACK?-MONO"))
    )
    (comp (ref "XTAL")
      (value "14.3044MHz")
      (footprint "eagle-import:HC49_S")
      (libsource (lib "eagle-import") (part "CRYSTALHC49S"))
    )
  )
  (nets
    (net (code "1") (name "+5V") (class "Default")
      (node (ref "7805") (pin "OUT") (pinfunction "OUT_OUT") (pintype "passive"))
      (node (ref "C1") (pin "+") (pinfunction "+_+") (pintype "passive"))
      (node (ref "C12") (pin "2") (pinfunction "2_2") (pintype "passive"))
      (node (ref "C13") (pin "2") (pinfunction "2_2") (pintype "passive"))
      (node (ref "C14") (pin "2") (pinfunction "2_2") (pintype "passive"))
      (node (ref "C15") (pin "1") (pinfunction "1_1") (pintype "passive"))
      (node (ref "C16") (pin "1") (pinfunction "1_1") (pintype "passive"))
      (node (ref "C18") (pin "1") (pinfunction "1_1") (pintype "passive"))
      (node (ref "C19") (pin "1") (pinfunction "1_1") (pintype "passive"))
      (node (ref "C20") (pin "1") (pinfunction "1_1") (pintype "passive"))
      (node (ref "C21") (pin "1") (pinfunction "1_1") (pintype "passive"))
      (node (ref "C22") (pin "2") (pinfunction "2_2") (pintype "passive"))
      (node (ref "C24") (pin "2") (pinfunction "2_2") (pintype "passive"))
      (node (ref "C29") (pin "2") (pinfunction "2_2") (pintype "passive"))
      (node (ref "C31") (pin "2") (pinfunction "2_2") (pintype "passive"))
      (node (ref "C32") (pin "2") (pinfunction "2_2") (pintype "passive"))
      (node (ref "C33") (pin "2") (pinfunction "2_2") (pintype "passive"))
      (node (ref "D13") (pin "C") (pinfunction "K_C") (pintype "bidirectional"))
      (node (ref "D15") (pin "C") (pinfunction "K_C") (pintype "bidirectional"))
      (node (ref "D17") (pin "C") (pinfunction "K_C") (pintype "bidirectional"))
      (node (ref "IC1") (pin "11") (pinfunction "VCC_11") (pintype "power_in"))
      (node (ref "IC10") (pin "16") (pinfunction "VCC_16") (pintype "power_in"))
      (node (ref "IC11") (pin "20") (pinfunction "VCC_20") (pintype "power_in"))
      (node (ref "IC12") (pin "3") (pinfunction "CR_BIAS_3") (pintype "input"))
      (node (ref "IC13") (pin "9") (pinfunction "A7_9") (pintype "input"))
      (node (ref "IC14") (pin "9") (pinfunction "A7_9") (pintype "input"))
      (node (ref "IC15") (pin "9") (pinfunction "A7_9") (pintype "input"))
      (node (ref "IC16") (pin "9") (pinfunction "A7_9") (pintype "input"))
      (node (ref "IC17") (pin "9") (pinfunction "A7_9") (pintype "input"))
      (node (ref "IC18") (pin "9") (pinfunction "A7_9") (pintype "input"))
      (node (ref "IC19") (pin "9") (pinfunction "A7_9") (pintype "input"))
      (node (ref "IC2") (pin "1") (pinfunction "VPP_1") (pintype "input"))
      (node (ref "IC2") (pin "28") (pinfunction "VCC_28") (pintype "power_in"))
      (node (ref "IC20") (pin "9") (pinfunction "A7_9") (pintype "input"))
      (node (ref "IC21") (pin "9") (pinfunction "VCC_9") (pintype "power_in"))
      (node (ref "IC22") (pin "9") (pinfunction "VCC_9") (pintype "power_in"))
      (node (ref "IC23") (pin "9") (pinfunction "VCC_9") (pintype "power_in"))
      (node (ref "IC24") (pin "9") (pinfunction "VCC_9") (pintype "power_in"))
      (node (ref "IC25") (pin "14") (pinfunction "VCC_14") (pintype "power_in"))
      (node (ref "IC26") (pin "1") (pinfunction "I0_1") (pintype "input"))
      (node (ref "IC26") (pin "14") (pinfunction "VCC_14") (pintype "power_in"))
      (node (ref "IC27") (pin "14") (pinfunction "VCC_14") (pintype "power_in"))
      (node (ref "IC28") (pin "14") (pinfunction "VCC_14") (pintype "power_in"))
      (node (ref "IC3") (pin "40") (pinfunction "VCC_40") (pintype "power_in"))
      (node (ref "IC4") (pin "10") (pinfunction "PRE_10") (pintype "input"))
      (node (ref "IC4") (pin "13") (pinfunction "CLR_13") (pintype "input"))
      (node (ref "IC4") (pin "14") (pinfunction "VCC_14") (pintype "power_in"))
      (node (ref "IC5") (pin "1") (pinfunction "CLR_1") (pintype "input"))
      (node (ref "IC5") (pin "10") (pinfunction "PRE_10") (pintype "input"))
      (node (ref "IC5") (pin "13") (pinfunction "CLR_13") (pintype "input"))
      (node (ref "IC5") (pin "14") (pinfunction "VCC_14") (pintype "power_in"))
      (node (ref "IC5") (pin "4") (pinfunction "PRE_4") (pintype "input"))
      (node (ref "IC6") (pin "16") (pinfunction "VCC_16") (pintype "power_in"))
      (node (ref "IC7") (pin "16") (pinfunction "VCC_16") (pintype "power_in"))
      (node (ref "IC8") (pin "16") (pinfunction "VCC_16") (pintype "power_in"))
      (node (ref "IC9") (pin "16") (pinfunction "VCC_16") (pintype "power_in"))
      (node (ref "J1") (pin "1") (pinfunction "1_1") (pintype "passive"))
      (node (ref "J2") (pin "1") (pinfunction "1_1") (pintype "passive"))
      (node (ref "Q1") (pin "3") (pinfunction "C_3") (pintype "passive"))
      (node (ref "R17") (pin "2") (pinfunction "2_2") (pintype "passive"))
      (node (ref "R18") (pin "2") (pinfunction "2_2") (pintype "passive"))
      (node (ref "R19") (pin "2") (pinfunction "2_2") (pintype "passive"))
      (node (ref "R20") (pin "2") (pinfunction "2_2") (pintype "passive"))
      (node (ref "R21") (pin "2") (pinfunction "2_2") (pintype "passive"))
      (node (ref "R22") (pin "2") (pinfunction "2_2") (pintype "passive"))
      (node (ref "R23") (pin "2") (pinfunction "2_2") (pintype "passive"))
      (node (ref "R24") (pin "2") (pinfunction "2_2") (pintype "passive"))
      (node (ref "R29") (pin "2") (pinfunction "2_2") (pintype "passive"))
      (node (ref "R30") (pin "1") (pinfunction "1_1") (pintype "passive"))
      (node (ref "R31") (pin "1") (pinfunction "1_1") (pintype "passive"))
      (node (ref "R32") (pin "1") (pinfunction "1_1") (pintype "passive"))
      (node (ref "R35") (pin "1") (pinfunction "1_1") (pintype "passive"))
      (node (ref "R36") (pin "1") (pinfunction "1_1") (pintype "passive"))
      (node (ref "R37") (pin "1") (pinfunction "1_1") (pintype "passive"))
      (node (ref "R38") (pin "1") (pinfunction "1_1") (pintype "passive"))
      (node (ref "R39") (pin "1") (pinfunction "1_1") (pintype "passive"))
      (node (ref "R40") (pin "2") (pinfunction "2_2") (pintype "passive"))
      (node (ref "R43") (pin "2") (pinfunction "2_2") (pintype "passive"))
      (node (ref "R48") (pin "2") (pinfunction "2_2") (pintype "passive"))
      (node (ref "R51") (pin "2") (pinfunction "2_2") (pintype "passive"))
      (node (ref "R74_") (pin "2") (pinfunction "2_2") (pintype "passive"))
      (node (ref "U$1") (pin "3A") (pinfunction "EDGE_3A") (pintype "bidirectional"))
    )
    (net (code "2") (name "+12V") (class "Default")
      (node (ref "C43") (pin "2") (pinfunction "2_2") (pintype "passive"))
      (node (ref "C53") (pin "+") (pinfunction "+_+") (pintype "passive"))
      (node (ref "D24") (pin "C") (pinfunction "K_C") (pintype "bidirectional"))
      (node (ref "IC11") (pin "5") (pinfunction "+12V_5") (pintype "power_in"))
      (node (ref "IC12") (pin "14") (pinfunction "RFVCC_14") (pintype "power_in"))
      (node (ref "IC12") (pin "16") (pinfunction "CRVCC_16") (pintype "power_in"))
      (node (ref "L1") (pin "2") (pinfunction "A_2") (pintype "passive"))
      (node (ref "R54") (pin "1") (pinfunction "1_1") (pintype "passive"))
      (node (ref "R57") (pin "1") (pinfunction "1_1") (pintype "passive"))
      (node (ref "R58") (pin "1") (pinfunction "1_1") (pintype "passive"))
      (node (ref "R59") (pin "1") (pinfunction "1_1") (pintype "passive"))
      (node (ref "R68") (pin "1") (pinfunction "1_1") (pintype "passive"))
      (node (ref "U$1") (pin "22B") (pinfunction "EDGE_22B") (pintype "bidirectional"))
    )
    (net (code "3") (name "-5V") (class "Default")
      (node (ref "C50") (pin "1") (pinfunction "1_1") (pintype "passive"))
      (node (ref "D21") (pin "A") (pinfunction "A_A") (pintype "bidirectional"))
      (node (ref "J3") (pin "1") (pinfunction "1_1") (pintype "passive"))
      (node (ref "R67") (pin "1") (pinfunction "1_1") (pintype "passive"))
      (node (ref "U$1") (pin "20B") (pinfunction "EDGE_20B") (pintype "bidirectional"))
    )
    (net (code "4") (name "/+12V_UNREG") (class "Default")
      (node (ref "C48") (pin "1") (pinfunction "1_1") (pintype "passive"))
      (node (ref "C51") (pin "1") (pinfunction "1_1") (pintype "passive"))
      (node (ref "Q5") (pin "E") (pinfunction "E_E") (pintype "passive"))
      (node (ref "Q6") (pin "E") (pinfunction "E_E") (pintype "passive"))
      (node (ref "U$1") (pin "23B") (pinfunction "EDGE_23B") (pintype "bidirectional"))
    )
    (net (code "5") (name "/A0") (class "Default")
      (node (ref "IC1") (pin "30") (pinfunction "A0_30") (pintype "output"))
      (node (ref "IC2") (pin "10") (pinfunction "A0_10") (pintype "input"))
      (node (ref "IC7") (pin "3") (pinfunction "1B_3") (pintype "input"))
      (node (ref "IC8") (pin "3") (pinfunction "1B_3") (pintype "input"))
      (node (ref "Q1") (pin "2") (pinfunction "B_2") (pintype "passive"))
      (node (ref "U$1") (pin "9A") (pinfunction "EDGE_9A") (pintype "bidirectional"))
    )
    (net (code "6") (name "/A1") (class "Default")
      (node (ref "IC1") (pin "31") (pinfunction "A1_31") (pintype "output"))
      (node (ref "IC2") (pin "9") (pinfunction "A1_9") (pintype "input"))
      (node (ref "IC7") (pin "6") (pinfunction "2B_6") (pintype "input"))
      (node (ref "IC8") (pin "6") (pinfunction "2B_6") (pintype "input"))
      (node (ref "U$1") (pin "10A") (pinfunction "EDGE_10A") (pintype "bidirectional"))
    )
    (net (code "7") (name "/A2") (class "Default")
      (node (ref "IC1") (pin "32") (pinfunction "A2_32") (pintype "output"))
      (node (ref "IC2") (pin "8") (pinfunction "A2_8") (pintype "input"))
      (node (ref "IC7") (pin "13") (pinfunction "4B_13") (pintype "input"))
      (node (ref "IC8") (pin "13") (pinfunction "4B_13") (pintype "input"))
      (node (ref "U$1") (pin "11A") (pinfunction "EDGE_11A") (pintype "bidirectional"))
    )
    (net (code "8") (name "/A3") (class "Default")
      (node (ref "IC1") (pin "33") (pinfunction "A3_33") (pintype "output"))
      (node (ref "IC2") (pin "7") (pinfunction "A3_7") (pintype "input"))
      (node (ref "IC7") (pin "10") (pinfunction "3B_10") (pintype "input"))
      (node (ref "IC8") (pin "10") (pinfunction "3B_10") (pintype "input"))
      (node (ref "U$1") (pin "12A") (pinfunction "EDGE_12A") (pintype "bidirectional"))
    )
    (net (code "9") (name "/A4") (class "Default")
      (node (ref "IC1") (pin "34") (pinfunction "A4_34") (pintype "output"))
      (node (ref "IC2") (pin "6") (pinfunction "A4_6") (pintype "input"))
      (node (ref "IC6") (pin "6") (pinfunction "2B_6") (pintype "input"))
      (node (ref "IC9") (pin "6") (pinfunction "2B_6") (pintype "input"))
      (node (ref "U$1") (pin "24A") (pinfunction "EDGE_24A") (pintype "bidirectional"))
    )
    (net (code "10") (name "/A5") (class "Default")
      (node (ref "IC1") (pin "35") (pinfunction "A5_35") (pintype "output"))
      (node (ref "IC2") (pin "5") (pinfunction "A5_5") (pintype "input"))
      (node (ref "IC6") (pin "13") (pinfunction "4B_13") (pintype "input"))
      (node (ref "IC9") (pin "13") (pinfunction "4B_13") (pintype "input"))
      (node (ref "U$1") (pin "23A") (pinfunction "EDGE_23A") (pintype "bidirectional"))
    )
    (net (code "11") (name "/A6") (class "Default")
      (node (ref "IC1") (pin "36") (pinfunction "A6_36") (pintype "output"))
      (node (ref "IC2") (pin "4") (pinfunction "A6_4") (pintype "input"))
      (node (ref "IC21") (pin "14") (pinfunction "A0_14") (pintype "input"))
      (node (ref "IC22") (pin "14") (pinfunction "A0_14") (pintype "input"))
      (node (ref "IC23") (pin "14") (pinfunction "A0_14") (pintype "input"))
      (node (ref "IC24") (pin "14") (pinfunction "A0_14") (pintype "input"))
      (node (ref "IC5") (pin "12") (pinfunction "D_12") (pintype "input"))
      (node (ref "IC9") (pin "10") (pinfunction "3B_10") (pintype "input"))
      (node (ref "U$1") (pin "22A") (pinfunction "EDGE_22A") (pintype "bidirectional"))
    )
    (net (code "12") (name "/A7") (class "Default")
      (node (ref "IC1") (pin "37") (pinfunction "A7_37") (pintype "output"))
      (node (ref "IC2") (pin "3") (pinfunction "A7_3") (pintype "input"))
      (node (ref "IC26") (pin "12") (pinfunction "I0_12") (pintype "input"))
      (node (ref "IC8") (pin "2") (pinfunction "1A_2") (pintype "input"))
      (node (ref "U$1") (pin "21A") (pinfunction "EDGE_21A") (pintype "bidirectional"))
    )
    (net (code "13") (name "/A7'") (class "Default")
      (node (ref "IC21") (pin "10") (pinfunction "A7_10") (pintype "input"))
      (node (ref "IC22") (pin "10") (pinfunction "A7_10") (pintype "input"))
      (node (ref "IC23") (pin "10") (pinfunction "A7_10") (pintype "input"))
      (node (ref "IC24") (pin "10") (pinfunction "A7_10") (pintype "input"))
      (node (ref "IC26") (pin "8") (pinfunction "O_8") (pintype "output"))
    )
    (net (code "14") (name "/A8") (class "Default")
      (node (ref "D2") (pin "C") (pinfunction "K_C") (pintype "bidirectional"))
      (node (ref "IC1") (pin "38") (pinfunction "A8_38") (pintype "output"))
      (node (ref "IC2") (pin "25") (pinfunction "A8_25") (pintype "input"))
      (node (ref "IC7") (pin "5") (pinfunction "2A_5") (pintype "input"))
      (node (ref "IC8") (pin "5") (pinfunction "2A_5") (pintype "input"))
      (node (ref "U$1") (pin "26B") (pinfunction "EDGE_26B") (pintype "bidirectional"))
    )
    (net (code "15") (name "/A8-1") (class "Default")
      (node (ref "IC21") (pin "7") (pinfunction "A5_7") (pintype "input"))
      (node (ref "IC22") (pin "7") (pinfunction "A5_7") (pintype "input"))
      (node (ref "IC23") (pin "7") (pinfunction "A5_7") (pintype "input"))
      (node (ref "IC24") (pin "7") (pinfunction "A5_7") (pintype "input"))
      (node (ref "IC7") (pin "7") (pinfunction "2Y_7") (pintype "output"))
    )
    (net (code "16") (name "/A9") (class "Default")
      (node (ref "D3") (pin "C") (pinfunction "K_C") (pintype "bidirectional"))
      (node (ref "IC1") (pin "39") (pinfunction "A9_39") (pintype "output"))
      (node (ref "IC2") (pin "24") (pinfunction "A9_24") (pintype "input"))
      (node (ref "IC7") (pin "14") (pinfunction "4A_14") (pintype "input"))
      (node (ref "IC8") (pin "14") (pinfunction "4A_14") (pintype "input"))
      (node (ref "U$1") (pin "27A") (pinfunction "EDGE_27A") (pintype "bidirectional"))
    )
    (net (code "17") (name "/A9-2") (class "Default")
      (node (ref "IC21") (pin "8") (pinfunction "A4_8") (pintype "input"))
      (node (ref "IC22") (pin "8") (pinfunction "A4_8") (pintype "input"))
      (node (ref "IC23") (pin "8") (pinfunction "A4_8") (pintype "input"))
      (node (ref "IC24") (pin "8") (pinfunction "A4_8") (pintype "input"))
      (node (ref "IC7") (pin "12") (pinfunction "4Y_12") (pintype "output"))
    )
    (net (code "18") (name "/A10") (class "Default")
      (node (ref "D4") (pin "C") (pinfunction "K_C") (pintype "bidirectional"))
      (node (ref "IC1") (pin "40") (pinfunction "A10_40") (pintype "output"))
      (node (ref "IC2") (pin "21") (pinfunction "A10_21") (pintype "input"))
      (node (ref "IC7") (pin "11") (pinfunction "3A_11") (pintype "input"))
      (node (ref "IC8") (pin "11") (pinfunction "3A_11") (pintype "input"))
      (node (ref "U$1") (pin "27B") (pinfunction "EDGE_27B") (pintype "bidirectional"))
    )
    (net (code "19") (name "/A10-3") (class "Default")
      (node (ref "IC21") (pin "11") (pinfunction "A3_11") (pintype "input"))
      (node (ref "IC22") (pin "11") (pinfunction "A3_11") (pintype "input"))
      (node (ref "IC23") (pin "11") (pinfunction "A3_11") (pintype "input"))
      (node (ref "IC24") (pin "11") (pinfunction "A3_11") (pintype "input"))
      (node (ref "IC7") (pin "9") (pinfunction "3Y_9") (pintype "output"))
    )
    (net (code "20") (name "/A11") (class "Default")
      (node (ref "D5") (pin "C") (pinfunction "K_C") (pintype "bidirectional"))
      (node (ref "IC1") (pin "1") (pinfunction "A11_1") (pintype "output"))
      (node (ref "IC2") (pin "23") (pinfunction "A11_23") (pintype "input"))
      (node (ref "IC6") (pin "5") (pinfunction "2A_5") (pintype "input"))
      (node (ref "IC9") (pin "5") (pinfunction "2A_5") (pintype "input"))
      (node (ref "U$1") (pin "28A") (pinfunction "EDGE_28A") (pintype "bidirectional"))
    )
    (net (code "21") (name "/A11-4") (class "Default")
      (node (ref "IC21") (pin "12") (pinfunction "A2_12") (pintype "input"))
      (node (ref "IC22") (pin "12") (pinfunction "A2_12") (pintype "input"))
      (node (ref "IC23") (pin "12") (pinfunction "A2_12") (pintype "input"))
      (node (ref "IC24") (pin "12") (pinfunction "A2_12") (pintype "input"))
      (node (ref "IC6") (pin "7") (pinfunction "2Y_7") (pintype "output"))
    )
    (net (code "22") (name "/A12") (class "Default")
      (node (ref "D6") (pin "C") (pinfunction "K_C") (pintype "bidirectional"))
      (node (ref "IC1") (pin "2") (pinfunction "A12_2") (pintype "output"))
      (node (ref "IC2") (pin "2") (pinfunction "A12_2") (pintype "input"))
      (node (ref "IC6") (pin "14") (pinfunction "4A_14") (pintype "input"))
      (node (ref "IC9") (pin "14") (pinfunction "4A_14") (pintype "input"))
      (node (ref "U$1") (pin "2A") (pinfunction "EDGE_2A") (pintype "bidirectional"))
    )
    (net (code "23") (name "/A12-5") (class "Default")
      (node (ref "IC21") (pin "13") (pinfunction "A1_13") (pintype "input"))
      (node (ref "IC22") (pin "13") (pinfunction "A1_13") (pintype "input"))
      (node (ref "IC23") (pin "13") (pinfunction "A1_13") (pintype "input"))
      (node (ref "IC24") (pin "13") (pinfunction "A1_13") (pintype "input"))
      (node (ref "IC6") (pin "12") (pinfunction "4Y_12") (pintype "output"))
    )
    (net (code "24") (name "/A13") (class "Default")
      (node (ref "D7") (pin "C") (pinfunction "K_C") (pintype "bidirectional"))
      (node (ref "IC1") (pin "3") (pinfunction "A13_3") (pintype "output"))
      (node (ref "IC2") (pin "26") (pinfunction "A13_26") (pintype "input"))
      (node (ref "IC7") (pin "2") (pinfunction "1A_2") (pintype "input"))
      (node (ref "IC9") (pin "11") (pinfunction "3A_11") (pintype "input"))
      (node (ref "U$1") (pin "2B") (pinfunction "EDGE_2B") (pintype "bidirectional"))
    )
    (net (code "25") (name "/A13-0") (class "Default")
      (node (ref "IC21") (pin "6") (pinfunction "A6_6") (pintype "input"))
      (node (ref "IC22") (pin "6") (pinfunction "A6_6") (pintype "input"))
      (node (ref "IC23") (pin "6") (pinfunction "A6_6") (pintype "input"))
      (node (ref "IC24") (pin "6") (pinfunction "A6_6") (pintype "input"))
      (node (ref "IC7") (pin "4") (pinfunction "1Y_4") (pintype "output"))
    )
    (net (code "26") (name "/A14") (class "Default")
      (node (ref "D12") (pin "A") (pinfunction "A_A") (pintype "bidirectional"))
      (node (ref "D8") (pin "C") (pinfunction "K_C") (pintype "bidirectional"))
      (node (ref "IC1") (pin "4") (pinfunction "A14_4") (pintype "output"))
      (node (ref "IC25") (pin "4") (pinfunction "I0_4") (pintype "input"))
      (node (ref "IC27") (pin "12") (pinfunction "I0_12") (pintype "input"))
      (node (ref "IC28") (pin "1") (pinfunction "I_1") (pintype "input"))
      (node (ref "IC3") (pin "37") (pinfunction "A14_37") (pintype "input"))
      (node (ref "U$1") (pin "1A") (pinfunction "EDGE_1A") (pintype "bidirectional"))
    )
    (net (code "27") (name "/A15") (class "Default")
      (node (ref "D11") (pin "A") (pinfunction "A_A") (pintype "bidirectional"))
      (node (ref "D9") (pin "C") (pinfunction "K_C") (pintype "bidirectional"))
      (node (ref "IC1") (pin "5") (pinfunction "A15_5") (pintype "output"))
      (node (ref "IC25") (pin "13") (pinfunction "I1_13") (pintype "input"))
      (node (ref "IC27") (pin "13") (pinfunction "I1_13") (pintype "input"))
      (node (ref "IC3") (pin "38") (pinfunction "A15_38") (pintype "input"))
      (node (ref "U$1") (pin "1B") (pinfunction "EDGE_1B") (pintype "bidirectional"))
    )
    (net (code "28") (name "/AA0") (class "Default")
      (node (ref "IC13") (pin "5") (pinfunction "A0_5") (pintype "input"))
      (node (ref "IC14") (pin "5") (pinfunction "A0_5") (pintype "input"))
      (node (ref "IC15") (pin "5") (pinfunction "A0_5") (pintype "input"))
      (node (ref "IC16") (pin "5") (pinfunction "A0_5") (pintype "input"))
      (node (ref "IC17") (pin "5") (pinfunction "A0_5") (pintype "input"))
      (node (ref "IC18") (pin "5") (pinfunction "A0_5") (pintype "input"))
      (node (ref "IC19") (pin "5") (pinfunction "A0_5") (pintype "input"))
      (node (ref "IC20") (pin "5") (pinfunction "A0_5") (pintype "input"))
      (node (ref "IC3") (pin "9") (pinfunction "A0_9") (pintype "output"))
      (node (ref "R9") (pin "1") (pinfunction "1_1") (pintype "passive"))
    )
    (net (code "29") (name "/AA1") (class "Default")
      (node (ref "IC13") (pin "7") (pinfunction "A1_7") (pintype "input"))
      (node (ref "IC14") (pin "7") (pinfunction "A1_7") (pintype "input"))
      (node (ref "IC15") (pin "7") (pinfunction "A1_7") (pintype "input"))
      (node (ref "IC16") (pin "7") (pinfunction "A1_7") (pintype "input"))
      (node (ref "IC17") (pin "7") (pinfunction "A1_7") (pintype "input"))
      (node (ref "IC18") (pin "7") (pinfunction "A1_7") (pintype "input"))
      (node (ref "IC19") (pin "7") (pinfunction "A1_7") (pintype "input"))
      (node (ref "IC20") (pin "7") (pinfunction "A1_7") (pintype "input"))
      (node (ref "IC3") (pin "7") (pinfunction "A1_7") (pintype "output"))
      (node (ref "R11") (pin "1") (pinfunction "1_1") (pintype "passive"))
    )
    (net (code "30") (name "/AA2") (class "Default")
      (node (ref "IC13") (pin "6") (pinfunction "A2_6") (pintype "input"))
      (node (ref "IC14") (pin "6") (pinfunction "A2_6") (pintype "input"))
      (node (ref "IC15") (pin "6") (pinfunction "A2_6") (pintype "input"))
      (node (ref "IC16") (pin "6") (pinfunction "A2_6") (pintype "input"))
      (node (ref "IC17") (pin "6") (pinfunction "A2_6") (pintype "input"))
      (node (ref "IC18") (pin "6") (pinfunction "A2_6") (pintype "input"))
      (node (ref "IC19") (pin "6") (pinfunction "A2_6") (pintype "input"))
      (node (ref "IC20") (pin "6") (pinfunction "A2_6") (pintype "input"))
      (node (ref "IC3") (pin "8") (pinfunction "A2_8") (pintype "output"))
      (node (ref "R10") (pin "1") (pinfunction "1_1") (pintype "passive"))
    )
    (net (code "31") (name "/AA3") (class "Default")
      (node (ref "IC13") (pin "12") (pinfunction "A3_12") (pintype "input"))
      (node (ref "IC14") (pin "12") (pinfunction "A3_12") (pintype "input"))
      (node (ref "IC15") (pin "12") (pinfunction "A3_12") (pintype "input"))
      (node (ref "IC16") (pin "12") (pinfunction "A3_12") (pintype "input"))
      (node (ref "IC17") (pin "12") (pinfunction "A3_12") (pintype "input"))
      (node (ref "IC18") (pin "12") (pinfunction "A3_12") (pintype "input"))
      (node (ref "IC19") (pin "12") (pinfunction "A3_12") (pintype "input"))
      (node (ref "IC20") (pin "12") (pinfunction "A3_12") (pintype "input"))
      (node (ref "IC3") (pin "4") (pinfunction "A3_4") (pintype "output"))
      (node (ref "R14") (pin "1") (pinfunction "1_1") (pintype "passive"))
    )
    (net (code "32") (name "/AA4") (class "Default")
      (node (ref "IC13") (pin "11") (pinfunction "A4_11") (pintype "input"))
      (node (ref "IC14") (pin "11") (pinfunction "A4_11") (pintype "input"))
      (node (ref "IC15") (pin "11") (pinfunction "A4_11") (pintype "input"))
      (node (ref "IC16") (pin "11") (pinfunction "A4_11") (pintype "input"))
      (node (ref "IC17") (pin "11") (pinfunction "A4_11") (pintype "input"))
      (node (ref "IC18") (pin "11") (pinfunction "A4_11") (pintype "input"))
      (node (ref "IC19") (pin "11") (pinfunction "A4_11") (pintype "input"))
      (node (ref "IC20") (pin "11") (pinfunction "A4_11") (pintype "input"))
      (node (ref "IC3") (pin "5") (pinfunction "A4_5") (pintype "output"))
      (node (ref "R13") (pin "1") (pinfunction "1_1") (pintype "passive"))
    )
    (net (code "33") (name "/AA5") (class "Default")
      (node (ref "IC13") (pin "10") (pinfunction "A5_10") (pintype "input"))
      (node (ref "IC14") (pin "10") (pinfunction "A5_10") (pintype "input"))
      (node (ref "IC15") (pin "10") (pinfunction "A5_10") (pintype "input"))
      (node (ref "IC16") (pin "10") (pinfunction "A5_10") (pintype "input"))
      (node (ref "IC17") (pin "10") (pinfunction "A5_10") (pintype "input"))
      (node (ref "IC18") (pin "10") (pinfunction "A5_10") (pintype "input"))
      (node (ref "IC19") (pin "10") (pinfunction "A5_10") (pintype "input"))
      (node (ref "IC20") (pin "10") (pinfunction "A5_10") (pintype "input"))
      (node (ref "IC3") (pin "6") (pinfunction "A5_6") (pintype "output"))
      (node (ref "R12") (pin "1") (pinfunction "1_1") (pintype "passive"))
    )
    (net (code "34") (name "/AA6") (class "Default")
      (node (ref "IC13") (pin "13") (pinfunction "A6_13") (pintype "input"))
      (node (ref "IC14") (pin "13") (pinfunction "A6_13") (pintype "input"))
      (node (ref "IC15") (pin "13") (pinfunction "A6_13") (pintype "input"))
      (node (ref "IC16") (pin "13") (pinfunction "A6_13") (pintype "input"))
      (node (ref "IC17") (pin "13") (pinfunction "A6_13") (pintype "input"))
      (node (ref "IC18") (pin "13") (pinfunction "A6_13") (pintype "input"))
      (node (ref "IC19") (pin "13") (pinfunction "A6_13") (pintype "input"))
      (node (ref "IC20") (pin "13") (pinfunction "A6_13") (pintype "input"))
      (node (ref "IC3") (pin "3") (pinfunction "A6_3") (pintype "output"))
      (node (ref "R15") (pin "1") (pinfunction "1_1") (pintype "passive"))
    )
    (net (code "35") (name "/CARRIER") (class "Default")
      (node (ref "C47") (pin "1") (pinfunction "1_1") (pintype "passive"))
      (node (ref "D17") (pin "A") (pinfunction "A_A") (pintype "bidirectional"))
      (node (ref "D18") (pin "C") (pinfunction "K_C") (pintype "bidirectional"))
      (node (ref "IC3") (pin "39") (pinfunction "CARRIER_39") (pintype "output"))
      (node (ref "R64") (pin "2") (pinfunction "2_2") (pintype "passive"))
      (node (ref "R71") (pin "2") (pinfunction "2_2") (pintype "passive"))
    )
    (net (code "36") (name "/CLK") (class "Default")
      (node (ref "C9") (pin "2") (pinfunction "2_2") (pintype "passive"))
      (node (ref "IC3") (pin "36") (pinfunction "CKOUT_36") (pintype "output"))
      (node (ref "R49") (pin "2") (pinfunction "2_2") (pintype "passive"))
      (node (ref "R51") (pin "1") (pinfunction "1_1") (pintype "passive"))
      (node (ref "U$1") (pin "8A") (pinfunction "EDGE_8A") (pintype "bidirectional"))
    )
    (net (code "37") (name "/D0") (class "Default")
      (node (ref "IC1") (pin "14") (pinfunction "D0_14") (pintype "bidirectional"))
      (node (ref "IC10") (pin "3") (pinfunction "Y1_3") (pintype "tri_state"))
      (node (ref "IC2") (pin "11") (pinfunction "O0_11") (pintype "tri_state"))
      (node (ref "IC21") (pin "2") (pinfunction "I/O1_2") (pintype "bidirectional"))
      (node (ref "IC23") (pin "2") (pinfunction "I/O1_2") (pintype "bidirectional"))
      (node (ref "R1") (pin "2") (pinfunction "2_2") (pintype "passive"))
      (node (ref "R17") (pin "1") (pinfunction "1_1") (pintype "passive"))
      (node (ref "U$1") (pin "6B") (pinfunction "EDGE_6B") (pintype "bidirectional"))
    )
    (net (code "38") (name "/D0'") (class "Default")
      (node (ref "IC20") (pin "14") (pinfunction "DO_14") (pintype "bidirectional"))
      (node (ref "IC20") (pin "2") (pinfunction "DI_2") (pintype "bidirectional"))
      (node (ref "IC3") (pin "25") (pinfunction "D0_25") (pintype "bidirectional"))
      (node (ref "R1") (pin "1") (pinfunction "1_1") (pintype "passive"))
    )
    (net (code "39") (name "/D1") (class "Default")
      (node (ref "IC1") (pin "15") (pinfunction "D1_15") (pintype "bidirectional"))
      (node (ref "IC10") (pin "5") (pinfunction "Y2_5") (pintype "tri_state"))
      (node (ref "IC2") (pin "12") (pinfunction "O1_12") (pintype "tri_state"))
      (node (ref "IC21") (pin "3") (pinfunction "I/O2_3") (pintype "bidirectional"))
      (node (ref "IC23") (pin "3") (pinfunction "I/O2_3") (pintype "bidirectional"))
      (node (ref "R18") (pin "1") (pinfunction "1_1") (pintype "passive"))
      (node (ref "R2") (pin "2") (pinfunction "2_2") (pintype "passive"))
      (node (ref "U$1") (pin "7B") (pinfunction "EDGE_7B") (pintype "bidirectional"))
    )
    (net (code "40") (name "/D1'") (class "Default")
      (node (ref "IC19") (pin "14") (pinfunction "DO_14") (pintype "bidirectional"))
      (node (ref "IC19") (pin "2") (pinfunction "DI_2") (pintype "bidirectional"))
      (node (ref "IC3") (pin "26") (pinfunction "D1_26") (pintype "bidirectional"))
      (node (ref "R2") (pin "1") (pinfunction "1_1") (pintype "passive"))
    )
    (net (code "41") (name "/D2") (class "Default")
      (node (ref "IC1") (pin "12") (pinfunction "D2_12") (pintype "bidirectional"))
      (node (ref "IC10") (pin "7") (pinfunction "Y3_7") (pintype "tri_state"))
      (node (ref "IC2") (pin "13") (pinfunction "O2_13") (pintype "tri_state"))
      (node (ref "IC21") (pin "15") (pinfunction "I/O3_15") (pintype "bidirectional"))
      (node (ref "IC23") (pin "15") (pinfunction "I/O3_15") (pintype "bidirectional"))
      (node (ref "R19") (pin "1") (pinfunction "1_1") (pintype "passive"))
      (node (ref "R3") (pin "2") (pinfunction "2_2") (pintype "passive"))
      (node (ref "U$1") (pin "8B") (pinfunction "EDGE_8B") (pintype "bidirectional"))
    )
    (net (code "42") (name "/D2'") (class "Default")
      (node (ref "IC18") (pin "14") (pinfunction "DO_14") (pintype "bidirectional"))
      (node (ref "IC18") (pin "2") (pinfunction "DI_2") (pintype "bidirectional"))
      (node (ref "IC3") (pin "27") (pinfunction "D2_27") (pintype "bidirectional"))
      (node (ref "R3") (pin "1") (pinfunction "1_1") (pintype "passive"))
    )
    (net (code "43") (name "/D3") (class "Default")
      (node (ref "IC1") (pin "8") (pinfunction "D3_8") (pintype "bidirectional"))
      (node (ref "IC10") (pin "9") (pinfunction "Y4_9") (pintype "tri_state"))
      (node (ref "IC2") (pin "15") (pinfunction "O3_15") (pintype "tri_state"))
      (node (ref "IC21") (pin "17") (pinfunction "I/O4_17") (pintype "bidirectional"))
      (node (ref "IC23") (pin "17") (pinfunction "I/O4_17") (pintype "bidirectional"))
      (node (ref "R20") (pin "1") (pinfunction "1_1") (pintype "passive"))
      (node (ref "R4") (pin "2") (pinfunction "2_2") (pintype "passive"))
      (node (ref "U$1") (pin "11B") (pinfunction "EDGE_11B") (pintype "bidirectional"))
    )
    (net (code "44") (name "/D3'") (class "Default")
      (node (ref "IC17") (pin "14") (pinfunction "DO_14") (pintype "bidirectional"))
      (node (ref "IC17") (pin "2") (pinfunction "DI_2") (pintype "bidirectional"))
      (node (ref "IC3") (pin "28") (pinfunction "D3_28") (pintype "bidirectional"))
      (node (ref "R4") (pin "1") (pinfunction "1_1") (pintype "passive"))
    )
    (net (code "45") (name "/D4") (class "Default")
      (node (ref "IC1") (pin "7") (pinfunction "D4_7") (pintype "bidirectional"))
      (node (ref "IC10") (pin "11") (pinfunction "Y5_11") (pintype "tri_state"))
      (node (ref "IC2") (pin "16") (pinfunction "O4_16") (pintype "tri_state"))
      (node (ref "IC22") (pin "2") (pinfunction "I/O1_2") (pintype "bidirectional"))
      (node (ref "IC24") (pin "2") (pinfunction "I/O1_2") (pintype "bidirectional"))
      (node (ref "R21") (pin "1") (pinfunction "1_1") (pintype "passive"))
      (node (ref "R5") (pin "2") (pinfunction "2_2") (pintype "passive"))
      (node (ref "U$1") (pin "12B") (pinfunction "EDGE_12B") (pintype "bidirectional"))
    )
    (net (code "46") (name "/D4'") (class "Default")
      (node (ref "IC16") (pin "14") (pinfunction "DO_14") (pintype "bidirectional"))
      (node (ref "IC16") (pin "2") (pinfunction "DI_2") (pintype "bidirectional"))
      (node (ref "IC3") (pin "29") (pinfunction "D4_29") (pintype "bidirectional"))
      (node (ref "R5") (pin "1") (pinfunction "1_1") (pintype "passive"))
    )
    (net (code "47") (name "/D5") (class "Default")
      (node (ref "IC1") (pin "9") (pinfunction "D5_9") (pintype "bidirectional"))
      (node (ref "IC2") (pin "17") (pinfunction "O5_17") (pintype "tri_state"))
      (node (ref "IC22") (pin "3") (pinfunction "I/O2_3") (pintype "bidirectional"))
      (node (ref "IC24") (pin "3") (pinfunction "I/O2_3") (pintype "bidirectional"))
      (node (ref "R22") (pin "1") (pinfunction "1_1") (pintype "passive"))
      (node (ref "R6") (pin "2") (pinfunction "2_2") (pintype "passive"))
      (node (ref "U$1") (pin "10B") (pinfunction "EDGE_10B") (pintype "bidirectional"))
    )
    (net (code "48") (name "/D5'") (class "Default")
      (node (ref "IC15") (pin "14") (pinfunction "DO_14") (pintype "bidirectional"))
      (node (ref "IC15") (pin "2") (pinfunction "DI_2") (pintype "bidirectional"))
      (node (ref "IC3") (pin "30") (pinfunction "D5_30") (pintype "bidirectional"))
      (node (ref "R6") (pin "1") (pinfunction "1_1") (pintype "passive"))
    )
    (net (code "49") (name "/D6") (class "Default")
      (node (ref "IC1") (pin "10") (pinfunction "D6_10") (pintype "bidirectional"))
      (node (ref "IC10") (pin "13") (pinfunction "Y6_13") (pintype "tri_state"))
      (node (ref "IC2") (pin "18") (pinfunction "O6_18") (pintype "tri_state"))
      (node (ref "IC22") (pin "15") (pinfunction "I/O3_15") (pintype "bidirectional"))
      (node (ref "IC24") (pin "15") (pinfunction "I/O3_15") (pintype "bidirectional"))
      (node (ref "R23") (pin "1") (pinfunction "1_1") (pintype "passive"))
      (node (ref "R7") (pin "2") (pinfunction "2_2") (pintype "passive"))
      (node (ref "U$1") (pin "9B") (pinfunction "EDGE_9B") (pintype "bidirectional"))
    )
    (net (code "50") (name "/D6'") (class "Default")
      (node (ref "IC14") (pin "14") (pinfunction "DO_14") (pintype "bidirectional"))
      (node (ref "IC14") (pin "2") (pinfunction "DI_2") (pintype "bidirectional"))
      (node (ref "IC3") (pin "31") (pinfunction "D6_31") (pintype "bidirectional"))
      (node (ref "R7") (pin "1") (pinfunction "1_1") (pintype "passive"))
    )
    (net (code "51") (name "/D7") (class "Default")
      (node (ref "D1") (pin "A") (pinfunction "A_A") (pintype "bidirectional"))
      (node (ref "IC1") (pin "13") (pinfunction "D7_13") (pintype "bidirectional"))
      (node (ref "IC2") (pin "19") (pinfunction "O7_19") (pintype "tri_state"))
      (node (ref "IC22") (pin "17") (pinfunction "I/O4_17") (pintype "bidirectional"))
      (node (ref "IC24") (pin "17") (pinfunction "I/O4_17") (pintype "bidirectional"))
      (node (ref "R24") (pin "1") (pinfunction "1_1") (pintype "passive"))
      (node (ref "R8") (pin "2") (pinfunction "2_2") (pintype "passive"))
      (node (ref "U$1") (pin "3B") (pinfunction "EDGE_3B") (pintype "bidirectional"))
    )
    (net (code "52") (name "/D7'") (class "Default")
      (node (ref "IC13") (pin "14") (pinfunction "DO_14") (pintype "bidirectional"))
      (node (ref "IC13") (pin "2") (pinfunction "DI_2") (pintype "bidirectional"))
      (node (ref "IC3") (pin "32") (pinfunction "D7_32") (pintype "bidirectional"))
      (node (ref "R8") (pin "1") (pinfunction "1_1") (pintype "passive"))
    )
    (net (code "53") (name "/MREQ'") (class "Default")
      (node (ref "D10") (pin "C") (pinfunction "K_C") (pintype "bidirectional"))
      (node (ref "IC3") (pin "15") (pinfunction "~{MREQ}_15") (pintype "input"))
      (node (ref "R34") (pin "2") (pinfunction "2_2") (pintype "passive"))
    )
    (net (code "54") (name "/N$33") (class "Default")
      (node (ref "C26") (pin "1") (pinfunction "1_1") (pintype "passive"))
      (node (ref "C27") (pin "1") (pinfunction "1_1") (pintype "passive"))
      (node (ref "IC13") (pin "1") (pinfunction "VBB_1") (pintype "input"))
      (node (ref "IC14") (pin "1") (pinfunction "VBB_1") (pintype "input"))
      (node (ref "IC15") (pin "1") (pinfunction "VBB_1") (pintype "input"))
      (node (ref "IC16") (pin "1") (pinfunction "VBB_1") (pintype "input"))
      (node (ref "IC17") (pin "1") (pinfunction "VBB_1") (pintype "input"))
      (node (ref "IC18") (pin "1") (pinfunction "VBB_1") (pintype "input"))
      (node (ref "IC19") (pin "1") (pinfunction "VBB_1") (pintype "input"))
      (node (ref "IC20") (pin "1") (pinfunction "VBB_1") (pintype "input"))
      (node (ref "J3") (pin "2") (pinfunction "2_2") (pintype "passive"))
    )
    (net (code "55") (name "/RESET") (class "Default")
      (node (ref "D10") (pin "A") (pinfunction "A_A") (pintype "bidirectional"))
      (node (ref "IC28") (pin "12") (pinfunction "O_12") (pintype "output"))
    )
    (net (code "56") (name "/SNDIN") (class "Default")
      (node (ref "C54") (pin "1") (pinfunction "1_1") (pintype "passive"))
      (node (ref "C57") (pin "1") (pinfunction "1_1") (pintype "passive"))
      (node (ref "D13") (pin "A") (pinfunction "A_A") (pintype "bidirectional"))
      (node (ref "D14") (pin "C") (pinfunction "C_C") (pintype "passive"))
      (node (ref "Q7") (pin "2") (pinfunction "B_2") (pintype "passive"))
      (node (ref "R40") (pin "1") (pinfunction "1_1") (pintype "passive"))
      (node (ref "R41") (pin "2") (pinfunction "2_2") (pintype "passive"))
      (node (ref "R42") (pin "2") (pinfunction "2_2") (pintype "passive"))
      (node (ref "TP3") (pin "1") (pinfunction "TP_1") (pintype "input"))
    )
    (net (code "57") (name "/{slash}INT") (class "Default")
      (node (ref "IC1") (pin "16") (pinfunction "~{INT}_16") (pintype "input"))
      (node (ref "R25") (pin "2") (pinfunction "2_2") (pintype "passive"))
      (node (ref "TP10") (pin "1") (pinfunction "TP_1") (pintype "input"))
      (node (ref "U$1") (pin "13B") (pinfunction "EDGE_13B") (pintype "bidirectional"))
    )
    (net (code "58") (name "/~{A}{slash}B") (class "Default")
      (node (ref "IC27") (pin "3") (pinfunction "O_3") (pintype "output"))
      (node (ref "IC6") (pin "1") (pinfunction "~{A}/B_1") (pintype "input"))
      (node (ref "IC7") (pin "1") (pinfunction "~{A}/B_1") (pintype "input"))
      (node (ref "R45") (pin "1") (pinfunction "1_1") (pintype "passive"))
    )
    (net (code "59") (name "/~{CAS0}") (class "Default")
      (node (ref "IC23") (pin "1") (pinfunction "~{OE}_1") (pintype "input"))
      (node (ref "IC23") (pin "16") (pinfunction "~{CAS}_16") (pintype "input"))
      (node (ref "IC24") (pin "1") (pinfunction "~{OE}_1") (pintype "input"))
      (node (ref "IC24") (pin "16") (pinfunction "~{CAS}_16") (pintype "input"))
      (node (ref "IC25") (pin "8") (pinfunction "O_8") (pintype "output"))
    )
    (net (code "60") (name "/~{CAS1}") (class "Default")
      (node (ref "IC21") (pin "1") (pinfunction "~{OE}_1") (pintype "input"))
      (node (ref "IC21") (pin "16") (pinfunction "~{CAS}_16") (pintype "input"))
      (node (ref "IC22") (pin "1") (pinfunction "~{OE}_1") (pintype "input"))
      (node (ref "IC22") (pin "16") (pinfunction "~{CAS}_16") (pintype "input"))
      (node (ref "IC25") (pin "6") (pinfunction "O_6") (pintype "output"))
    )
    (net (code "61") (name "/~{IORQGE}") (class "Default")
      (node (ref "IC3") (pin "2") (pinfunction "~{CS}_2") (pintype "input"))
      (node (ref "Q1") (pin "1") (pinfunction "E_1") (pintype "passive"))
      (node (ref "R27") (pin "2") (pinfunction "2_2") (pintype "passive"))
      (node (ref "U$1") (pin "13A") (pinfunction "EDGE_13A") (pintype "bidirectional"))
    )
    (net (code "62") (name "/~{IORQ}") (class "Default")
      (node (ref "IC1") (pin "20") (pinfunction "~{IORQ}_20") (pintype "output"))
      (node (ref "R27") (pin "1") (pinfunction "1_1") (pintype "passive"))
      (node (ref "U$1") (pin "17B") (pinfunction "EDGE_17B") (pintype "bidirectional"))
    )
    (net (code "63") (name "/~{KBD}") (class "Default")
      (node (ref "D1") (pin "C") (pinfunction "K_C") (pintype "bidirectional"))
      (node (ref "IC10") (pin "1") (pinfunction "G1_1") (pintype "input"))
      (node (ref "IC3") (pin "10") (pinfunction "~{KBD}_10") (pintype "output"))
    )
    (net (code "64") (name "/~{MREQ}") (class "Default")
      (node (ref "IC1") (pin "19") (pinfunction "~{MREQ}_19") (pintype "output"))
      (node (ref "IC2") (pin "22") (pinfunction "~{OE}_22") (pintype "input"))
      (node (ref "IC27") (pin "4") (pinfunction "I0_4") (pintype "input"))
      (node (ref "R34") (pin "1") (pinfunction "1_1") (pintype "passive"))
      (node (ref "U$1") (pin "16B") (pinfunction "EDGE_16B") (pintype "bidirectional"))
    )
    (net (code "65") (name "/~{RAS}") (class "Default")
      (node (ref "IC21") (pin "5") (pinfunction "~{RAS}_5") (pintype "input"))
      (node (ref "IC22") (pin "5") (pinfunction "~{RAS}_5") (pintype "input"))
      (node (ref "IC23") (pin "5") (pinfunction "~{RAS}_5") (pintype "input"))
      (node (ref "IC24") (pin "5") (pinfunction "~{RAS}_5") (pintype "input"))
      (node (ref "IC27") (pin "6") (pinfunction "O_6") (pintype "output"))
      (node (ref "IC27") (pin "9") (pinfunction "I0_9") (pintype "input"))
      (node (ref "R28") (pin "1") (pinfunction "1_1") (pintype "passive"))
    )
    (net (code "66") (name "/~{RD}") (class "Default")
      (node (ref "IC1") (pin "21") (pinfunction "~{RD}_21") (pintype "output"))
      (node (ref "IC25") (pin "2") (pinfunction "I1_2") (pintype "input"))
      (node (ref "IC3") (pin "17") (pinfunction "~{RD}_17") (pintype "input"))
      (node (ref "J1") (pin "3") (pinfunction "3_3") (pintype "passive"))
      (node (ref "U$1") (pin "18B") (pinfunction "EDGE_18B") (pintype "bidirectional"))
    )
    (net (code "67") (name "/~{RESET}") (class "Default")
      (node (ref "C17") (pin "1") (pinfunction "1_1") (pintype "passive"))
      (node (ref "IC1") (pin "26") (pinfunction "~{RESET}_26") (pintype "input"))
      (node (ref "IC28") (pin "13") (pinfunction "I_13") (pintype "input"))
      (node (ref "R29") (pin "1") (pinfunction "1_1") (pintype "passive"))
      (node (ref "U$1") (pin "20A") (pinfunction "EDGE_20A") (pintype "bidirectional"))
    )
    (net (code "68") (name "/~{RFSH}") (class "Default")
      (node (ref "IC1") (pin "28") (pinfunction "~{RFSH}_28") (pintype "output"))
      (node (ref "IC26") (pin "13") (pinfunction "I1_13") (pintype "input"))
      (node (ref "IC26") (pin "2") (pinfunction "I1_2") (pintype "input"))
      (node (ref "IC5") (pin "11") (pinfunction "CLK_11") (pintype "input"))
      (node (ref "U$1") (pin "25B") (pinfunction "EDGE_25B") (pintype "bidirectional"))
    )
    (net (code "69") (name "/~{ROMCS}") (class "Default")
      (node (ref "IC2") (pin "20") (pinfunction "~{CE}_20") (pintype "input"))
      (node (ref "R26") (pin "2") (pinfunction "2_2") (pintype "passive"))
      (node (ref "TP9") (pin "1") (pinfunction "TP_1") (pintype "input"))
      (node (ref "U$1") (pin "25A") (pinfunction "EDGE_25A") (pintype "bidirectional"))
    )
    (net (code "70") (name "/~{ULAINT}") (class "Default")
      (node (ref "IC3") (pin "34") (pinfunction "~{INT}_34") (pintype "output"))
      (node (ref "R25") (pin "1") (pinfunction "1_1") (pintype "passive"))
    )
    (net (code "71") (name "/~{VCAS}") (class "Default")
      (node (ref "IC13") (pin "15") (pinfunction "~{CAS}_15") (pintype "input"))
      (node (ref "IC14") (pin "15") (pinfunction "~{CAS}_15") (pintype "input"))
      (node (ref "IC15") (pin "15") (pinfunction "~{CAS}_15") (pintype "input"))
      (node (ref "IC16") (pin "15") (pinfunction "~{CAS}_15") (pintype "input"))
      (node (ref "IC17") (pin "15") (pinfunction "~{CAS}_15") (pintype "input"))
      (node (ref "IC18") (pin "15") (pinfunction "~{CAS}_15") (pintype "input"))
      (node (ref "IC19") (pin "15") (pinfunction "~{CAS}_15") (pintype "input"))
      (node (ref "IC20") (pin "15") (pinfunction "~{CAS}_15") (pintype "input"))
      (node (ref "IC3") (pin "12") (pinfunction "~{VCAS}_12") (pintype "output"))
      (node (ref "TP5") (pin "1") (pinfunction "TP_1") (pintype "input"))
    )
    (net (code "72") (name "/~{VRAS}") (class "Default")
      (node (ref "IC13") (pin "4") (pinfunction "~{RAS}_4") (pintype "input"))
      (node (ref "IC14") (pin "4") (pinfunction "~{RAS}_4") (pintype "input"))
      (node (ref "IC15") (pin "4") (pinfunction "~{RAS}_4") (pintype "input"))
      (node (ref "IC16") (pin "4") (pinfunction "~{RAS}_4") (pintype "input"))
      (node (ref "IC17") (pin "4") (pinfunction "~{RAS}_4") (pintype "input"))
      (node (ref "IC18") (pin "4") (pinfunction "~{RAS}_4") (pintype "input"))
      (node (ref "IC19") (pin "4") (pinfunction "~{RAS}_4") (pintype "input"))
      (node (ref "IC20") (pin "4") (pinfunction "~{RAS}_4") (pintype "input"))
      (node (ref "IC3") (pin "13") (pinfunction "~{VRAS}_13") (pintype "output"))
      (node (ref "R16") (pin "2") (pinfunction "2_2") (pintype "passive"))
      (node (ref "TP4") (pin "1") (pinfunction "TP_1") (pintype "input"))
    )
    (net (code "73") (name "/~{VWR}") (class "Default")
      (node (ref "IC13") (pin "3") (pinfunction "~{WE}_3") (pintype "input"))
      (node (ref "IC14") (pin "3") (pinfunction "~{WE}_3") (pintype "input"))
      (node (ref "IC15") (pin "3") (pinfunction "~{WE}_3") (pintype "input"))
      (node (ref "IC16") (pin "3") (pinfunction "~{WE}_3") (pintype "input"))
      (node (ref "IC17") (pin "3") (pinfunction "~{WE}_3") (pintype "input"))
      (node (ref "IC18") (pin "3") (pinfunction "~{WE}_3") (pintype "input"))
      (node (ref "IC19") (pin "3") (pinfunction "~{WE}_3") (pintype "input"))
      (node (ref "IC20") (pin "3") (pinfunction "~{WE}_3") (pintype "input"))
      (node (ref "IC3") (pin "14") (pinfunction "~{VWR}_14") (pintype "output"))
      (node (ref "TP6") (pin "1") (pinfunction "TP_1") (pintype "input"))
    )
    (net (code "74") (name "/~{WR}") (class "Default")
      (node (ref "IC1") (pin "22") (pinfunction "~{WR}_22") (pintype "output"))
      (node (ref "IC21") (pin "4") (pinfunction "~{WE}_4") (pintype "input"))
      (node (ref "IC22") (pin "4") (pinfunction "~{WE}_4") (pintype "input"))
      (node (ref "IC23") (pin "4") (pinfunction "~{WE}_4") (pintype "input"))
      (node (ref "IC24") (pin "4") (pinfunction "~{WE}_4") (pintype "input"))
      (node (ref "IC25") (pin "1") (pinfunction "I0_1") (pintype "input"))
      (node (ref "IC3") (pin "16") (pinfunction "~{WR}_16") (pintype "input"))
      (node (ref "U$1") (pin "19B") (pinfunction "EDGE_19B") (pintype "bidirectional"))
    )
    (net (code "75") (name "GND") (class "Default")
      (node (ref "7805") (pin "GND") (pinfunction "GND_GND") (pintype "input"))
      (node (ref "C1") (pin "-") (pinfunction "-_-") (pintype "passive"))
      (node (ref "C10") (pin "2") (pinfunction "2_2") (pintype "passive"))
      (node (ref "C11") (pin "2") (pinfunction "2_2") (pintype "passive"))
      (node (ref "C12") (pin "1") (pinfunction "1_1") (pintype "passive"))
      (node (ref "C13") (pin "1") (pinfunction "1_1") (pintype "passive"))
      (node (ref "C14") (pin "1") (pinfunction "1_1") (pintype "passive"))
      (node (ref "C15") (pin "2") (pinfunction "2_2") (pintype "passive"))
      (node (ref "C16") (pin "2") (pinfunction "2_2") (pintype "passive"))
      (node (ref "C17") (pin "2") (pinfunction "2_2") (pintype "passive"))
      (node (ref "C18") (pin "2") (pinfunction "2_2") (pintype "passive"))
      (node (ref "C19") (pin "2") (pinfunction "2_2") (pintype "passive"))
      (node (ref "C2") (pin "-") (pinfunction "-_-") (pintype "passive"))
      (node (ref "C20") (pin "2") (pinfunction "2_2") (pintype "passive"))
      (node (ref "C21") (pin "2") (pinfunction "2_2") (pintype "passive"))
      (node (ref "C22") (pin "1") (pinfunction "1_1") (pintype "passive"))
      (node (ref "C23") (pin "2") (pinfunction "2_2") (pintype "passive"))
      (node (ref "C24") (pin "1") (pinfunction "1_1") (pintype "passive"))
      (node (ref "C25") (pin "2") (pinfunction "2_2") (pintype "passive"))
      (node (ref "C26") (pin "2") (pinfunction "2_2") (pintype "passive"))
      (node (ref "C27") (pin "2") (pinfunction "2_2") (pintype "passive"))
      (node (ref "C28") (pin "2") (pinfunction "2_2") (pintype "passive"))
      (node (ref "C29") (pin "1") (pinfunction "1_1") (pintype "passive"))
      (node (ref "C3") (pin "1") (pinfunction "1_1") (pintype "passive"))
      (node (ref "C30") (pin "2") (pinfunction "2_2") (pintype "passive"))
      (node (ref "C31") (pin "1") (pinfunction "1_1") (pintype "passive"))
      (node (ref "C32") (pin "1") (pinfunction "1_1") (pintype "passive"))
      (node (ref "C33") (pin "1") (pinfunction "1_1") (pintype "passive"))
      (node (ref "C40") (pin "1") (pinfunction "1_1") (pintype "passive"))
      (node (ref "C43") (pin "1") (pinfunction "1_1") (pintype "passive"))
      (node (ref "C44") (pin "2") (pinfunction "2_2") (pintype "passive"))
      (node (ref "C45") (pin "2") (pinfunction "2_2") (pintype "passive"))
      (node (ref "C46") (pin "2") (pinfunction "2_2") (pintype "passive"))
      (node (ref "C49") (pin "+") (pinfunction "+_+") (pintype "passive"))
      (node (ref "C50") (pin "2") (pinfunction "2_2") (pintype "passive"))
      (node (ref "C52") (pin "-") (pinfunction "-_-") (pintype "passive"))
      (node (ref "C53") (pin "-") (pinfunction "-_-") (pintype "passive"))
      (node (ref "C56") (pin "1") (pinfunction "1_1") (pintype "passive"))
      (node (ref "C57") (pin "2") (pinfunction "2_2") (pintype "passive"))
      (node (ref "C6") (pin "1") (pinfunction "1_1") (pintype "passive"))
      (node (ref "C8") (pin "1") (pinfunction "1_1") (pintype "passive"))
      (node (ref "D14") (pin "A") (pinfunction "A_A") (pintype "passive"))
      (node (ref "D16") (pin "A") (pinfunction "A_A") (pintype "bidirectional"))
      (node (ref "D18") (pin "A") (pinfunction "A_A") (pintype "bidirectional"))
      (node (ref "D20") (pin "C") (pinfunction "K_C") (pintype "bidirectional"))
      (node (ref "D21") (pin "C") (pinfunction "K_C") (pintype "bidirectional"))
      (node (ref "D24") (pin "A") (pinfunction "A_A") (pintype "bidirectional"))
      (node (ref "EAR") (pin "RING") (pinfunction "SHIELD_RING") (pintype "passive"))
      (node (ref "IC1") (pin "29") (pinfunction "GND_29") (pintype "power_in"))
      (node (ref "IC10") (pin "15") (pinfunction "G2_15") (pintype "input"))
      (node (ref "IC10") (pin "8") (pinfunction "GND_8") (pintype "power_in"))
      (node (ref "IC11") (pin "10") (pinfunction "GND_10") (pintype "power_in"))
      (node (ref "IC12") (pin "5") (pinfunction "GND_5") (pintype "power_in"))
      (node (ref "IC13") (pin "16") (pinfunction "VSS_16") (pintype "power_in"))
      (node (ref "IC14") (pin "16") (pinfunction "VSS_16") (pintype "power_in"))
      (node (ref "IC15") (pin "16") (pinfunction "VSS_16") (pintype "power_in"))
      (node (ref "IC16") (pin "16") (pinfunction "VSS_16") (pintype "power_in"))
      (node (ref "IC17") (pin "16") (pinfunction "VSS_16") (pintype "power_in"))
      (node (ref "IC18") (pin "16") (pinfunction "VSS_16") (pintype "power_in"))
      (node (ref "IC19") (pin "16") (pinfunction "VSS_16") (pintype "power_in"))
      (node (ref "IC2") (pin "14") (pinfunction "GND_14") (pintype "power_in"))
      (node (ref "IC20") (pin "16") (pinfunction "VSS_16") (pintype "power_in"))
      (node (ref "IC21") (pin "18") (pinfunction "GND_18") (pintype "power_in"))
      (node (ref "IC22") (pin "18") (pinfunction "GND_18") (pintype "power_in"))
      (node (ref "IC23") (pin "18") (pinfunction "GND_18") (pintype "power_in"))
      (node (ref "IC24") (pin "18") (pinfunction "GND_18") (pintype "power_in"))
      (node (ref "IC25") (pin "7") (pinfunction "GND_7") (pintype "power_in"))
      (node (ref "IC26") (pin "7") (pinfunction "GND_7") (pintype "power_in"))
      (node (ref "IC27") (pin "5") (pinfunction "I1_5") (pintype "input"))
      (node (ref "IC27") (pin "7") (pinfunction "GND_7") (pintype "power_in"))
      (node (ref "IC28") (pin "7") (pinfunction "GND_7") (pintype "power_in"))
      (node (ref "IC3") (pin "20") (pinfunction "GND_20") (pintype "power_in"))
      (node (ref "IC4") (pin "7") (pinfunction "GND_7") (pintype "power_in"))
      (node (ref "IC5") (pin "7") (pinfunction "GND_7") (pintype "power_in"))
      (node (ref "IC6") (pin "15") (pinfunction "G_15") (pintype "input"))
      (node (ref "IC6") (pin "8") (pinfunction "GND_8") (pintype "power_in"))
      (node (ref "IC7") (pin "15") (pinfunction "G_15") (pintype "input"))
      (node (ref "IC7") (pin "8") (pinfunction "GND_8") (pintype "power_in"))
      (node (ref "IC8") (pin "15") (pinfunction "G_15") (pintype "input"))
      (node (ref "IC8") (pin "8") (pinfunction "GND_8") (pintype "power_in"))
      (node (ref "IC9") (pin "15") (pinfunction "G_15") (pintype "input"))
      (node (ref "IC9") (pin "8") (pinfunction "GND_8") (pintype "power_in"))
      (node (ref "MIC") (pin "RING") (pinfunction "SHIELD_RING") (pintype "passive"))
      (node (ref "Q2") (pin "1") (pinfunction "E_1") (pintype "passive"))
      (node (ref "Q4") (pin "1") (pinfunction "E_1") (pintype "passive"))
      (node (ref "Q6") (pin "C") (pinfunction "C_C") (pintype "passive"))
      (node (ref "Q7") (pin "1") (pinfunction "E_1") (pintype "passive"))
      (node (ref "R33") (pin "2") (pinfunction "2_2") (pintype "passive"))
      (node (ref "R41") (pin "1") (pinfunction "1_1") (pintype "passive"))
      (node (ref "R47") (pin "1") (pinfunction "1_1") (pintype "passive"))
      (node (ref "R50") (pin "1") (pinfunction "1_1") (pintype "passive"))
      (node (ref "R53") (pin "2") (pinfunction "2_2") (pintype "passive"))
      (node (ref "R55") (pin "2") (pinfunction "2_2") (pintype "passive"))
      (node (ref "R60") (pin "2") (pinfunction "2_2") (pintype "passive"))
      (node (ref "R65") (pin "2") (pinfunction "2_2") (pintype "passive"))
      (node (ref "R69") (pin "1") (pinfunction "1_1") (pintype "passive"))
      (node (ref "R70") (pin "1") (pinfunction "1_1") (pintype "passive"))
      (node (ref "R73_") (pin "2") (pinfunction "2_2") (pintype "passive"))
      (node (ref "U$1") (pin "14A") (pinfunction "EDGE_14A") (pintype "bidirectional"))
      (node (ref "U$1") (pin "6A") (pinfunction "EDGE_6A") (pintype "bidirectional"))
      (node (ref "U$1") (pin "7A") (pinfunction "EDGE_7A") (pintype "bidirectional"))
      (node (ref "X2") (pin "RING") (pinfunction "SHIELD_RING") (pintype "passive"))
    )
    (net (code "76") (name "Net-(C5-Pad1)") (class "Default")
      (node (ref "C5") (pin "1") (pinfunction "1_1") (pintype "passive"))
      (node (ref "R42") (pin "1") (pinfunction "1_1") (pintype "passive"))
    )
    (net (code "77") (name "Net-(C5-Pad2)") (class "Default")
      (node (ref "C5") (pin "2") (pinfunction "2_2") (pintype "passive"))
      (node (ref "EAR") (pin "NC") (pinfunction "NC_NC") (pintype "passive"))
      (node (ref "EAR") (pin "TIP") (pinfunction "TIP_TIP") (pintype "passive"))
      (node (ref "R70") (pin "2") (pinfunction "2_2") (pintype "passive"))
    )
    (net (code "78") (name "Net-(C7-Pad1)") (class "Default")
      (node (ref "C7") (pin "1") (pinfunction "1_1") (pintype "passive"))
      (node (ref "XTAL") (pin "2") (pinfunction "2_2") (pintype "passive"))
    )
    (net (code "79") (name "Net-(C8-Pad2)") (class "Default")
      (node (ref "C8") (pin "2") (pinfunction "2_2") (pintype "passive"))
      (node (ref "Q3") (pin "B") (pinfunction "B_B") (pintype "passive"))
      (node (ref "R44") (pin "2") (pinfunction "2_2") (pintype "passive"))
      (node (ref "XTAL") (pin "1") (pinfunction "1_1") (pintype "passive"))
    )
    (net (code "80") (name "Net-(C34-Pad2)") (class "Default")
      (node (ref "C34") (pin "2") (pinfunction "2_2") (pintype "passive"))
      (node (ref "R52") (pin "2") (pinfunction "2_2") (pintype "passive"))
    )
    (net (code "81") (name "Net-(C36-Pad2)") (class "Default")
      (node (ref "C36") (pin "2") (pinfunction "2_2") (pintype "passive"))
      (node (ref "C54") (pin "2") (pinfunction "2_2") (pintype "passive"))
      (node (ref "C55") (pin "1") (pinfunction "1_1") (pintype "passive"))
      (node (ref "D25_") (pin "A") (pinfunction "A_A") (pintype "bidirectional"))
      (node (ref "R53") (pin "1") (pinfunction "1_1") (pintype "passive"))
      (node (ref "R54") (pin "2") (pinfunction "2_2") (pintype "passive"))
    )
    (net (code "82") (name "Net-(C37-Pad1)") (class "Default")
      (node (ref "C37") (pin "1") (pinfunction "1_1") (pintype "passive"))
      (node (ref "C38") (pin "2") (pinfunction "2_2") (pintype "passive"))
      (node (ref "R55") (pin "1") (pinfunction "1_1") (pintype "passive"))
    )
    (net (code "83") (name "Net-(C38-Pad1)") (class "Default")
      (node (ref "C38") (pin "1") (pinfunction "1_1") (pintype "passive"))
      (node (ref "C39") (pin "2") (pinfunction "2_2") (pintype "passive"))
      (node (ref "R56") (pin "1") (pinfunction "1_1") (pintype "passive"))
    )
    (net (code "84") (name "Net-(C39-Pad1)") (class "Default")
      (node (ref "C39") (pin "1") (pinfunction "1_1") (pintype "passive"))
      (node (ref "L2") (pin "2") (pinfunction "2_2") (pintype "passive"))
    )
    (net (code "85") (name "Net-(C49-Pad-)") (class "Default")
      (node (ref "C49") (pin "-") (pinfunction "-_-") (pintype "passive"))
      (node (ref "D19") (pin "A") (pinfunction "A_A") (pintype "bidirectional"))
      (node (ref "R67") (pin "2") (pinfunction "2_2") (pintype "passive"))
    )
    (net (code "86") (name "Net-(C56-Pad2)") (class "Default")
      (node (ref "C56") (pin "2") (pinfunction "2_2") (pintype "passive"))
      (node (ref "L2") (pin "1") (pinfunction "1_1") (pintype "passive"))
      (node (ref "R71") (pin "1") (pinfunction "1_1") (pintype "passive"))
      (node (ref "R72") (pin "2") (pinfunction "2_2") (pintype "passive"))
    )
    (net (code "87") (name "Net-(D2-PadA)") (class "Default")
      (node (ref "D2") (pin "A") (pinfunction "A_A") (pintype "bidirectional"))
      (node (ref "KB2") (pin "3") (pinfunction "3_3") (pintype "passive"))
    )
    (net (code "88") (name "Net-(D3-PadA)") (class "Default")
      (node (ref "D3") (pin "A") (pinfunction "A_A") (pintype "bidirectional"))
      (node (ref "KB2") (pin "6") (pinfunction "6_6") (pintype "passive"))
    )
    (net (code "89") (name "Net-(D4-PadA)") (class "Default")
      (node (ref "D4") (pin "A") (pinfunction "A_A") (pintype "bidirectional"))
      (node (ref "KB2") (pin "7") (pinfunction "7_7") (pintype "passive"))
    )
    (net (code "90") (name "Net-(D7-PadA)") (class "Default")
      (node (ref "D7") (pin "A") (pinfunction "A_A") (pintype "bidirectional"))
      (node (ref "KB2") (pin "4") (pinfunction "4_4") (pintype "passive"))
    )
    (net (code "91") (name "Net-(D8-PadA)") (class "Default")
      (node (ref "D8") (pin "A") (pinfunction "A_A") (pintype "bidirectional"))
      (node (ref "KB2") (pin "2") (pinfunction "2_2") (pintype "passive"))
    )
    (net (code "92") (name "Net-(D9-PadA)") (class "Default")
      (node (ref "D9") (pin "A") (pinfunction "A_A") (pintype "bidirectional"))
      (node (ref "KB2") (pin "1") (pinfunction "1_1") (pintype "passive"))
    )
    (net (code "93") (name "Net-(D11-K)") (class "Default")
      (node (ref "D11") (pin "C") (pinfunction "K_C") (pintype "bidirectional"))
      (node (ref "D12") (pin "C") (pinfunction "K_C") (pintype "bidirectional"))
      (node (ref "IC27") (pin "11") (pinfunction "O_11") (pintype "output"))
      (node (ref "R26") (pin "1") (pinfunction "1_1") (pintype "passive"))
      (node (ref "R33") (pin "1") (pinfunction "1_1") (pintype "passive"))
    )
    (net (code "94") (name "Net-(D16-K)") (class "Default")
      (node (ref "C36") (pin "1") (pinfunction "1_1") (pintype "passive"))
      (node (ref "D15") (pin "A") (pinfunction "A_A") (pintype "bidirectional"))
      (node (ref "D16") (pin "C") (pinfunction "K_C") (pintype "bidirectional"))
      (node (ref "IC3") (pin "24") (pinfunction "BEEP_24") (pintype "output"))
      (node (ref "TP7") (pin "1") (pinfunction "TP_1") (pintype "input"))
    )
    (net (code "95") (name "Net-(D19-K)") (class "Default")
      (node (ref "C48") (pin "2") (pinfunction "2_2") (pintype "passive"))
      (node (ref "D19") (pin "C") (pinfunction "K_C") (pintype "bidirectional"))
      (node (ref "D20") (pin "A") (pinfunction "A_A") (pintype "bidirectional"))
    )
    (net (code "96") (name "Net-(D22-K)") (class "Default")
      (node (ref "C51") (pin "2") (pinfunction "2_2") (pintype "passive"))
      (node (ref "D22") (pin "C") (pinfunction "K_C") (pintype "bidirectional"))
      (node (ref "D23") (pin "A") (pinfunction "A_A") (pintype "bidirectional"))
    )
    (net (code "97") (name "Net-(D23-K)") (class "Default")
      (node (ref "C52") (pin "+") (pinfunction "+_+") (pintype "passive"))
      (node (ref "D23") (pin "C") (pinfunction "K_C") (pintype "bidirectional"))
      (node (ref "R68") (pin "2") (pinfunction "2_2") (pintype "passive"))
    )
    (net (code "98") (name "Net-(D27-K)") (class "Default")
      (node (ref "D25") (pin "C") (pinfunction "C_C") (pintype "passive"))
      (node (ref "D26") (pin "C") (pinfunction "C_C") (pintype "passive"))
      (node (ref "D27") (pin "C") (pinfunction "K_C") (pintype "bidirectional"))
      (node (ref "IC3") (pin "18") (pinfunction "BRIGHT_18") (pintype "output"))
    )
    (net (code "99") (name "Net-(IC1-CLK)") (class "Default")
      (node (ref "IC1") (pin "6") (pinfunction "CLK_6") (pintype "input"))
      (node (ref "Q2") (pin "3") (pinfunction "C_3") (pintype "passive"))
      (node (ref "R48") (pin "1") (pinfunction "1_1") (pintype "passive"))
      (node (ref "TP1") (pin "1") (pinfunction "TP_1") (pintype "input"))
    )
    (net (code "100") (name "Net-(IC1-~{BUSAK})") (class "Default")
      (node (ref "IC1") (pin "23") (pinfunction "~{BUSAK}_23") (pintype "output"))
      (node (ref "U$1") (pin "26A") (pinfunction "EDGE_26A") (pintype "bidirectional"))
    )
    (net (code "101") (name "Net-(IC1-~{BUSRQ})") (class "Default")
      (node (ref "IC1") (pin "25") (pinfunction "~{BUSRQ}_25") (pintype "input"))
      (node (ref "R30") (pin "2") (pinfunction "2_2") (pintype "passive"))
      (node (ref "U$1") (pin "19A") (pinfunction "EDGE_19A") (pintype "bidirectional"))
    )
    (net (code "102") (name "Net-(IC1-~{HALT})") (class "Default")
      (node (ref "IC1") (pin "18") (pinfunction "~{HALT}_18") (pintype "output"))
      (node (ref "U$1") (pin "15B") (pinfunction "EDGE_15B") (pintype "bidirectional"))
    )
    (net (code "103") (name "Net-(IC1-~{M1})") (class "Default")
      (node (ref "IC1") (pin "27") (pinfunction "~{M1}_27") (pintype "output"))
      (node (ref "U$1") (pin "24B") (pinfunction "EDGE_24B") (pintype "bidirectional"))
    )
    (net (code "104") (name "Net-(IC1-~{NMI})") (class "Default")
      (node (ref "IC1") (pin "17") (pinfunction "~{NMI}_17") (pintype "input"))
      (node (ref "R31") (pin "2") (pinfunction "2_2") (pintype "passive"))
      (node (ref "U$1") (pin "14B") (pinfunction "EDGE_14B") (pintype "bidirectional"))
    )
    (net (code "105") (name "Net-(IC1-~{WAIT})") (class "Default")
      (node (ref "IC1") (pin "24") (pinfunction "~{WAIT}_24") (pintype "input"))
      (node (ref "R32") (pin "2") (pinfunction "2_2") (pintype "passive"))
      (node (ref "U$1") (pin "21B") (pinfunction "EDGE_21B") (pintype "bidirectional"))
    )
    (net (code "106") (name "Net-(IC2-~{PGM})") (class "Default")
      (node (ref "IC2") (pin "27") (pinfunction "~{PGM}_27") (pintype "input"))
      (node (ref "J1") (pin "2") (pinfunction "2_2") (pintype "passive"))
    )
    (net (code "107") (name "Net-(IC3-MIC)") (class "Default")
      (node (ref "IC3") (pin "23") (pinfunction "MIC_23") (pintype "output"))
      (node (ref "R46") (pin "2") (pinfunction "2_2") (pintype "passive"))
    )
    (net (code "108") (name "Net-(IC4B-D)") (class "Default")
      (node (ref "IC4") (pin "12") (pinfunction "D_12") (pintype "input"))
      (node (ref "IC4") (pin "8") (pinfunction "~{Q}_8") (pintype "output"))
    )
    (net (code "109") (name "Net-(IC5A-CLK)") (class "Default")
      (node (ref "IC5") (pin "3") (pinfunction "CLK_3") (pintype "input"))
      (node (ref "IC5") (pin "9") (pinfunction "Q_9") (pintype "output"))
    )
    (net (code "110") (name "Net-(IC5A-D)") (class "Default")
      (node (ref "IC5") (pin "2") (pinfunction "D_2") (pintype "input"))
      (node (ref "IC5") (pin "6") (pinfunction "~{Q}_6") (pintype "output"))
    )
    (net (code "111") (name "Net-(IC8A-1Y)") (class "Default")
      (node (ref "IC8") (pin "4") (pinfunction "1Y_4") (pintype "output"))
      (node (ref "R15") (pin "2") (pinfunction "2_2") (pintype "passive"))
    )
    (net (code "112") (name "Net-(IC8A-2Y)") (class "Default")
      (node (ref "IC8") (pin "7") (pinfunction "2Y_7") (pintype "output"))
      (node (ref "R14") (pin "2") (pinfunction "2_2") (pintype "passive"))
    )
    (net (code "113") (name "Net-(IC8A-3Y)") (class "Default")
      (node (ref "IC8") (pin "9") (pinfunction "3Y_9") (pintype "output"))
      (node (ref "R12") (pin "2") (pinfunction "2_2") (pintype "passive"))
    )
    (net (code "114") (name "Net-(IC8A-4Y)") (class "Default")
      (node (ref "IC8") (pin "12") (pinfunction "4Y_12") (pintype "output"))
      (node (ref "R13") (pin "2") (pinfunction "2_2") (pintype "passive"))
    )
    (net (code "115") (name "Net-(IC8A-~{A}{slash}B)") (class "Default")
      (node (ref "IC8") (pin "1") (pinfunction "~{A}/B_1") (pintype "input"))
      (node (ref "IC9") (pin "1") (pinfunction "~{A}/B_1") (pintype "input"))
      (node (ref "R16") (pin "1") (pinfunction "1_1") (pintype "passive"))
    )
    (net (code "116") (name "Net-(IC9A-2Y)") (class "Default")
      (node (ref "IC9") (pin "7") (pinfunction "2Y_7") (pintype "output"))
      (node (ref "R11") (pin "2") (pinfunction "2_2") (pintype "passive"))
    )
    (net (code "117") (name "Net-(IC9A-3Y)") (class "Default")
      (node (ref "IC9") (pin "9") (pinfunction "3Y_9") (pintype "output"))
      (node (ref "R9") (pin "2") (pinfunction "2_2") (pintype "passive"))
    )
    (net (code "118") (name "Net-(IC9A-4Y)") (class "Default")
      (node (ref "IC9") (pin "12") (pinfunction "4Y_12") (pintype "output"))
      (node (ref "R10") (pin "2") (pinfunction "2_2") (pintype "passive"))
    )
    (net (code "119") (name "Net-(IC10A-A1)") (class "Default")
      (node (ref "IC10") (pin "2") (pinfunction "A1_2") (pintype "input"))
      (node (ref "KB1") (pin "5") (pinfunction "5_5") (pintype "passive"))
      (node (ref "P") (pin "6") (pinfunction "M_6") (pintype "passive"))
      (node (ref "R39") (pin "2") (pinfunction "2_2") (pintype "passive"))
    )
    (net (code "120") (name "Net-(IC10A-A2)") (class "Default")
      (node (ref "IC10") (pin "4") (pinfunction "A2_4") (pintype "input"))
      (node (ref "KB1") (pin "4") (pinfunction "4_4") (pintype "passive"))
      (node (ref "P") (pin "1") (pinfunction "M_1") (pintype "passive"))
      (node (ref "R38") (pin "2") (pinfunction "2_2") (pintype "passive"))
    )
    (net (code "121") (name "Net-(IC10A-A3)") (class "Default")
      (node (ref "IC10") (pin "6") (pinfunction "A3_6") (pintype "input"))
      (node (ref "KB1") (pin "3") (pinfunction "3_3") (pintype "passive"))
      (node (ref "P") (pin "2") (pinfunction "M_2") (pintype "passive"))
      (node (ref "R35") (pin "2") (pinfunction "2_2") (pintype "passive"))
    )
    (net (code "122") (name "Net-(IC10A-A4)") (class "Default")
      (node (ref "IC10") (pin "10") (pinfunction "A4_10") (pintype "input"))
      (node (ref "KB1") (pin "2") (pinfunction "2_2") (pintype "passive"))
      (node (ref "P") (pin "4") (pinfunction "M_4") (pintype "passive"))
      (node (ref "R36") (pin "2") (pinfunction "2_2") (pintype "passive"))
    )
    (net (code "123") (name "Net-(IC10A-A5)") (class "Default")
      (node (ref "IC10") (pin "12") (pinfunction "A5_12") (pintype "input"))
      (node (ref "KB1") (pin "1") (pinfunction "1_1") (pintype "passive"))
      (node (ref "P") (pin "3") (pinfunction "M_3") (pintype "passive"))
      (node (ref "R37") (pin "2") (pinfunction "2_2") (pintype "passive"))
    )
    (net (code "124") (name "Net-(IC10A-A6)") (class "Default")
      (node (ref "IC10") (pin "14") (pinfunction "A6_14") (pintype "input"))
      (node (ref "Q7") (pin "3") (pinfunction "C_3") (pintype "passive"))
      (node (ref "R74_") (pin "1") (pinfunction "1_1") (pintype "passive"))
    )
    (net (code "125") (name "Net-(IC11-B-Y)") (class "Default")
      (node (ref "C45") (pin "1") (pinfunction "1_1") (pintype "passive"))
      (node (ref "IC11") (pin "4") (pinfunction "B-Y_4") (pintype "output"))
      (node (ref "IC12") (pin "4") (pinfunction "B-Y_4") (pintype "input"))
    )
    (net (code "126") (name "Net-(IC11-B1)") (class "Default")
      (node (ref "IC11") (pin "17") (pinfunction "B3_17") (pintype "input"))
      (node (ref "IC11") (pin "19") (pinfunction "B1_19") (pintype "input"))
      (node (ref "IC3") (pin "22") (pinfunction "BLUE_22") (pintype "output"))
      (node (ref "R75") (pin "2") (pinfunction "2_2") (pintype "passive"))
    )
    (net (code "127") (name "Net-(IC11-B2)") (class "Default")
      (node (ref "D27") (pin "A") (pinfunction "A_A") (pintype "bidirectional"))
      (node (ref "IC11") (pin "18") (pinfunction "B2_18") (pintype "input"))
      (node (ref "R75") (pin "1") (pinfunction "1_1") (pintype "passive"))
    )
    (net (code "128") (name "Net-(IC11-BLANK)") (class "Default")
      (node (ref "IC11") (pin "8") (pinfunction "SYNC_8") (pintype "input"))
      (node (ref "IC11") (pin "9") (pinfunction "BLANK_9") (pintype "input"))
      (node (ref "IC3") (pin "33") (pinfunction "SYNC_33") (pintype "output"))
      (node (ref "TP8") (pin "1") (pinfunction "TP_1") (pintype "input"))
    )
    (net (code "129") (name "Net-(IC11-CREF)") (class "Default")
      (node (ref "C46") (pin "1") (pinfunction "1_1") (pintype "passive"))
      (node (ref "IC11") (pin "7") (pinfunction "CREF_7") (pintype "input"))
      (node (ref "IC12") (pin "12") (pinfunction "Y_12") (pintype "input"))
    )
    (net (code "130") (name "Net-(IC11-G1)") (class "Default")
      (node (ref "IC11") (pin "14") (pinfunction "G3_14") (pintype "input"))
      (node (ref "IC11") (pin "16") (pinfunction "G1_16") (pintype "input"))
      (node (ref "IC3") (pin "19") (pinfunction "GREEN_19") (pintype "output"))
      (node (ref "R73") (pin "2") (pinfunction "2_2") (pintype "passive"))
    )
    (net (code "131") (name "Net-(IC11-G2)") (class "Default")
      (node (ref "D25") (pin "A") (pinfunction "A_A") (pintype "passive"))
      (node (ref "IC11") (pin "15") (pinfunction "G2_15") (pintype "input"))
      (node (ref "R73") (pin "1") (pinfunction "1_1") (pintype "passive"))
    )
    (net (code "132") (name "Net-(IC11-GATE)") (class "Default")
      (node (ref "IC11") (pin "1") (pinfunction "GATE_1") (pintype "input"))
      (node (ref "IC28") (pin "6") (pinfunction "O_6") (pintype "output"))
    )
    (net (code "133") (name "Net-(IC11-H{slash}2)") (class "Default")
      (node (ref "IC11") (pin "2") (pinfunction "H/2_2") (pintype "input"))
      (node (ref "IC4") (pin "9") (pinfunction "Q_9") (pintype "output"))
    )
    (net (code "134") (name "Net-(IC11-R-Y)") (class "Default")
      (node (ref "C44") (pin "1") (pinfunction "1_1") (pintype "passive"))
      (node (ref "IC11") (pin "3") (pinfunction "R-Y_3") (pintype "output"))
      (node (ref "IC12") (pin "2") (pinfunction "R-Y_2") (pintype "input"))
    )
    (net (code "135") (name "Net-(IC11-R1)") (class "Default")
      (node (ref "IC11") (pin "11") (pinfunction "R3_11") (pintype "input"))
      (node (ref "IC11") (pin "13") (pinfunction "R1_13") (pintype "input"))
      (node (ref "IC3") (pin "21") (pinfunction "RED_21") (pintype "output"))
      (node (ref "R74") (pin "2") (pinfunction "2_2") (pintype "passive"))
    )
    (net (code "136") (name "Net-(IC11-R2)") (class "Default")
      (node (ref "D26") (pin "A") (pinfunction "A_A") (pintype "passive"))
      (node (ref "IC11") (pin "12") (pinfunction "R2_12") (pintype "input"))
      (node (ref "R74") (pin "1") (pinfunction "1_1") (pintype "passive"))
    )
    (net (code "137") (name "Net-(IC11-Y)") (class "Default")
      (node (ref "IC11") (pin "6") (pinfunction "Y_6") (pintype "output"))
      (node (ref "R63") (pin "2") (pinfunction "2_2") (pintype "passive"))
    )
    (net (code "138") (name "Net-(IC12-CHB_O)") (class "Default")
      (node (ref "C42") (pin "1") (pinfunction "1_1") (pintype "passive"))
      (node (ref "IC12") (pin "10") (pinfunction "CHB_O_10") (pintype "input"))
      (node (ref "R59") (pin "2") (pinfunction "2_2") (pintype "passive"))
    )
    (net (code "139") (name "Net-(IC12-CR_LAG)") (class "Default")
      (node (ref "C40") (pin "2") (pinfunction "2_2") (pintype "passive"))
      (node (ref "IC12") (pin "18") (pinfunction "CR_LAG_18") (pintype "output"))
      (node (ref "R56") (pin "2") (pinfunction "2_2") (pintype "passive"))
    )
    (net (code "140") (name "Net-(IC12-CR_LEAD)") (class "Default")
      (node (ref "C37") (pin "2") (pinfunction "2_2") (pintype "passive"))
      (node (ref "IC12") (pin "1") (pinfunction "CR_LEAD_1") (pintype "input"))
    )
    (net (code "141") (name "Net-(IC12-CR_OSC)") (class "Default")
      (node (ref "IC12") (pin "17") (pinfunction "CR_OSC_17") (pintype "input"))
      (node (ref "R72") (pin "1") (pinfunction "1_1") (pintype "passive"))
      (node (ref "R73_") (pin "1") (pinfunction "1_1") (pintype "passive"))
    )
    (net (code "142") (name "Net-(IC12-CR_SUBC)") (class "Default")
      (node (ref "C34") (pin "1") (pinfunction "1_1") (pintype "passive"))
      (node (ref "IC12") (pin "13") (pinfunction "CR_SUBC_13") (pintype "input"))
      (node (ref "R63") (pin "1") (pinfunction "1_1") (pintype "passive"))
    )
    (net (code "143") (name "Net-(IC12-SNDTK)") (class "Default")
      (node (ref "D25_") (pin "K") (pinfunction "K_K") (pintype "bidirectional"))
      (node (ref "IC12") (pin "15") (pinfunction "SNDTK_15") (pintype "input"))
      (node (ref "L1") (pin "4") (pinfunction "E_4") (pintype "passive"))
      (node (ref "R52") (pin "1") (pinfunction "1_1") (pintype "passive"))
    )
    (net (code "144") (name "Net-(IC12-TNKA1)") (class "Default")
      (node (ref "IC12") (pin "8") (pinfunction "TNKA1_8") (pintype "output"))
      (node (ref "IC12") (pin "9") (pinfunction "TNKA2_9") (pintype "input"))
    )
    (net (code "145") (name "Net-(IC12-TNKB1)") (class "Default")
      (node (ref "C41") (pin "2") (pinfunction "2_2") (pintype "passive"))
      (node (ref "IC12") (pin "6") (pinfunction "TNKB1_6") (pintype "output"))
      (node (ref "L3") (pin "1") (pinfunction "1_1") (pintype "passive"))
      (node (ref "R57") (pin "2") (pinfunction "2_2") (pintype "passive"))
    )
    (net (code "146") (name "Net-(IC12-TNKB2)") (class "Default")
      (node (ref "C41") (pin "1") (pinfunction "1_1") (pintype "passive"))
      (node (ref "IC12") (pin "7") (pinfunction "TNKB2_7") (pintype "input"))
      (node (ref "L3") (pin "2") (pinfunction "2_2") (pintype "passive"))
      (node (ref "R58") (pin "2") (pinfunction "2_2") (pintype "passive"))
    )
    (net (code "147") (name "Net-(IC25A-O)") (class "Default")
      (node (ref "IC25") (pin "12") (pinfunction "I0_12") (pintype "input"))
      (node (ref "IC25") (pin "3") (pinfunction "O_3") (pintype "output"))
    )
    (net (code "148") (name "Net-(IC25B-I1)") (class "Default")
      (node (ref "IC25") (pin "10") (pinfunction "I1_10") (pintype "input"))
      (node (ref "IC25") (pin "5") (pinfunction "I1_5") (pintype "input"))
      (node (ref "IC28") (pin "4") (pinfunction "O_4") (pintype "output"))
    )
    (net (code "149") (name "Net-(IC25C-I0)") (class "Default")
      (node (ref "IC25") (pin "9") (pinfunction "I0_9") (pintype "input"))
      (node (ref "IC28") (pin "2") (pinfunction "O_2") (pintype "output"))
    )
    (net (code "150") (name "Net-(IC25D-O)") (class "Default")
      (node (ref "IC25") (pin "11") (pinfunction "O_11") (pintype "output"))
      (node (ref "IC27") (pin "1") (pinfunction "I0_1") (pintype "input"))
    )
    (net (code "151") (name "Net-(IC26A-O)") (class "Default")
      (node (ref "IC26") (pin "3") (pinfunction "O_3") (pintype "output"))
      (node (ref "IC26") (pin "4") (pinfunction "I0_4") (pintype "input"))
    )
    (net (code "152") (name "Net-(IC26B-I1)") (class "Default")
      (node (ref "IC26") (pin "5") (pinfunction "I1_5") (pintype "input"))
      (node (ref "IC5") (pin "5") (pinfunction "Q_5") (pintype "output"))
    )
    (net (code "153") (name "Net-(IC26B-O)") (class "Default")
      (node (ref "IC26") (pin "6") (pinfunction "O_6") (pintype "output"))
      (node (ref "IC26") (pin "9") (pinfunction "I0_9") (pintype "input"))
    )
    (net (code "154") (name "Net-(IC26C-I1)") (class "Default")
      (node (ref "IC26") (pin "10") (pinfunction "I1_10") (pintype "input"))
      (node (ref "IC26") (pin "11") (pinfunction "O_11") (pintype "output"))
    )
    (net (code "155") (name "Net-(IC27A-I1)") (class "Default")
      (node (ref "C10") (pin "1") (pinfunction "1_1") (pintype "passive"))
      (node (ref "IC27") (pin "2") (pinfunction "I1_2") (pintype "input"))
      (node (ref "R28") (pin "2") (pinfunction "2_2") (pintype "passive"))
    )
    (net (code "156") (name "Net-(IC27C-I1)") (class "Default")
      (node (ref "C11") (pin "1") (pinfunction "1_1") (pintype "passive"))
      (node (ref "IC27") (pin "10") (pinfunction "I1_10") (pintype "input"))
      (node (ref "R45") (pin "2") (pinfunction "2_2") (pintype "passive"))
    )
    (net (code "157") (name "Net-(IC27C-O)") (class "Default")
      (node (ref "IC27") (pin "8") (pinfunction "O_8") (pintype "output"))
      (node (ref "IC28") (pin "3") (pinfunction "I_3") (pintype "input"))
    )
    (net (code "158") (name "Net-(IC28C-I)") (class "Default")
      (node (ref "IC28") (pin "5") (pinfunction "I_5") (pintype "input"))
      (node (ref "IC3") (pin "35") (pinfunction "GATE_35") (pintype "output"))
      (node (ref "IC4") (pin "11") (pinfunction "CLK_11") (pintype "input"))
    )
    (net (code "159") (name "Net-(IC28D-I)") (class "Default")
      (node (ref "C6") (pin "2") (pinfunction "2_2") (pintype "passive"))
      (node (ref "C7") (pin "2") (pinfunction "2_2") (pintype "passive"))
      (node (ref "IC28") (pin "9") (pinfunction "I_9") (pintype "input"))
      (node (ref "Q3") (pin "C") (pinfunction "C_C") (pintype "passive"))
      (node (ref "R43") (pin "1") (pinfunction "1_1") (pintype "passive"))
      (node (ref "R44") (pin "1") (pinfunction "1_1") (pintype "passive"))
    )
    (net (code "160") (name "Net-(IC28D-O)") (class "Default")
      (node (ref "IC28") (pin "11") (pinfunction "I_11") (pintype "input"))
      (node (ref "IC28") (pin "8") (pinfunction "O_8") (pintype "output"))
      (node (ref "JP") (pin "3") (pinfunction "3_3") (pintype "passive"))
    )
    (net (code "161") (name "Net-(IC28E-O)") (class "Default")
      (node (ref "IC28") (pin "10") (pinfunction "O_10") (pintype "output"))
      (node (ref "IC3") (pin "11") (pinfunction "CLK_11") (pintype "input"))
      (node (ref "JP") (pin "1") (pinfunction "1_1") (pintype "passive"))
      (node (ref "JP") (pin "2") (pinfunction "2_2") (pintype "passive"))
      (node (ref "TP2") (pin "1") (pinfunction "TP_1") (pintype "input"))
    )
    (net (code "162") (name "Net-(MIC-PadNC)") (class "Default")
      (node (ref "MIC") (pin "NC") (pinfunction "NC_NC") (pintype "passive"))
      (node (ref "MIC") (pin "TIP") (pinfunction "TIP_TIP") (pintype "passive"))
      (node (ref "R46") (pin "1") (pinfunction "1_1") (pintype "passive"))
      (node (ref "R69") (pin "2") (pinfunction "2_2") (pintype "passive"))
    )
    (net (code "163") (name "Net-(PE-M)") (class "Default")
      (node (ref "D6") (pin "A") (pinfunction "A_A") (pintype "bidirectional"))
      (node (ref "KB2") (pin "5") (pinfunction "5_5") (pintype "passive"))
      (node (ref "P") (pin "5") (pinfunction "M_5") (pintype "passive"))
      (node (ref "P") (pin "8") (pinfunction "M_8") (pintype "passive"))
      (node (ref "P") (pin "9") (pinfunction "M_9") (pintype "passive"))
    )
    (net (code "164") (name "Net-(PG-M)") (class "Default")
      (node (ref "D5") (pin "A") (pinfunction "A_A") (pintype "bidirectional"))
      (node (ref "KB2") (pin "8") (pinfunction "8_8") (pintype "passive"))
      (node (ref "P") (pin "7") (pinfunction "M_7") (pintype "passive"))
    )
    (net (code "165") (name "Net-(Q2-B)") (class "Default")
      (node (ref "C9") (pin "1") (pinfunction "1_1") (pintype "passive"))
      (node (ref "Q2") (pin "2") (pinfunction "B_2") (pintype "passive"))
      (node (ref "R49") (pin "1") (pinfunction "1_1") (pintype "passive"))
      (node (ref "R50") (pin "2") (pinfunction "2_2") (pintype "passive"))
    )
    (net (code "166") (name "Net-(Q3-PadE)") (class "Default")
      (node (ref "Q3") (pin "E") (pinfunction "E_E") (pintype "passive"))
      (node (ref "R47") (pin "2") (pinfunction "2_2") (pintype "passive"))
    )
    (net (code "167") (name "Net-(Q4-B)") (class "Default")
      (node (ref "C47") (pin "2") (pinfunction "2_2") (pintype "passive"))
      (node (ref "Q4") (pin "2") (pinfunction "B_2") (pintype "passive"))
      (node (ref "R64") (pin "1") (pinfunction "1_1") (pintype "passive"))
      (node (ref "R65") (pin "1") (pinfunction "1_1") (pintype "passive"))
    )
    (net (code "168") (name "Net-(Q4-C)") (class "Default")
      (node (ref "Q4") (pin "3") (pinfunction "C_3") (pintype "passive"))
      (node (ref "Q5") (pin "B") (pinfunction "B_B") (pintype "passive"))
      (node (ref "Q6") (pin "B") (pinfunction "B_B") (pintype "passive"))
      (node (ref "R66") (pin "2") (pinfunction "2_2") (pintype "passive"))
    )
    (net (code "169") (name "Net-(U$1Y-EDGE)") (class "Default")
      (node (ref "C55") (pin "2") (pinfunction "2_2") (pintype "passive"))
      (node (ref "U$1") (pin "4B") (pinfunction "EDGE_4B") (pintype "bidirectional"))
    )
    (net (code "170") (name "Net-(VIDEO(RF)-TP)") (class "Default")
      (node (ref "C42") (pin "2") (pinfunction "2_2") (pintype "passive"))
      (node (ref "R60") (pin "1") (pinfunction "1_1") (pintype "passive"))
      (node (ref "VIDEO(RF)") (pin "1") (pinfunction "TP_1") (pintype "input"))
    )
    (net (code "171") (name "V+") (class "Default")
      (node (ref "7805") (pin "IN") (pinfunction "IN_IN") (pintype "input"))
      (node (ref "C2") (pin "+") (pinfunction "+_+") (pintype "passive"))
      (node (ref "C3") (pin "2") (pinfunction "2_2") (pintype "passive"))
      (node (ref "D22") (pin "A") (pinfunction "A_A") (pintype "bidirectional"))
      (node (ref "J2") (pin "3") (pinfunction "3_3") (pintype "passive"))
      (node (ref "Q5") (pin "C") (pinfunction "C_C") (pintype "passive"))
      (node (ref "R66") (pin "1") (pinfunction "1_1") (pintype "passive"))
      (node (ref "U$1") (pin "4A") (pinfunction "EDGE_4A") (pintype "bidirectional"))
      (node (ref "X2") (pin "NC") (pinfunction "NC_NC") (pintype "passive"))
      (node (ref "X2") (pin "TIP") (pinfunction "TIP_TIP") (pintype "passive"))
    )
    (net (code "172") (name "VDD") (class "Default")
      (node (ref "C23") (pin "1") (pinfunction "1_1") (pintype "passive"))
      (node (ref "C25") (pin "1") (pinfunction "1_1") (pintype "passive"))
      (node (ref "C28") (pin "1") (pinfunction "1_1") (pintype "passive"))
      (node (ref "C30") (pin "1") (pinfunction "1_1") (pintype "passive"))
      (node (ref "IC13") (pin "8") (pinfunction "VDD_8") (pintype "power_in"))
      (node (ref "IC14") (pin "8") (pinfunction "VDD_8") (pintype "power_in"))
      (node (ref "IC15") (pin "8") (pinfunction "VDD_8") (pintype "power_in"))
      (node (ref "IC16") (pin "8") (pinfunction "VDD_8") (pintype "power_in"))
      (node (ref "IC17") (pin "8") (pinfunction "VDD_8") (pintype "power_in"))
      (node (ref "IC18") (pin "8") (pinfunction "VDD_8") (pintype "power_in"))
      (node (ref "IC19") (pin "8") (pinfunction "VDD_8") (pintype "power_in"))
      (node (ref "IC20") (pin "8") (pinfunction "VDD_8") (pintype "power_in"))
      (node (ref "J2") (pin "2") (pinfunction "2_2") (pintype "passive"))
    )
    (net (code "173") (name "unconnected-(IC3-~{50}{slash}60HZ-Pad1)") (class "Default")
      (node (ref "IC3") (pin "1") (pinfunction "~{50}/60HZ_1") (pintype "input"))
    )
    (net (code "174") (name "unconnected-(IC4A-CLK-Pad3)") (class "Default")
      (node (ref "IC4") (pin "3") (pinfunction "CLK_3") (pintype "input"))
    )
    (net (code "175") (name "unconnected-(IC4A-CLR-Pad1)") (class "Default")
      (node (ref "IC4") (pin "1") (pinfunction "CLR_1") (pintype "input"))
    )
    (net (code "176") (name "unconnected-(IC4A-D-Pad2)") (class "Default")
      (node (ref "IC4") (pin "2") (pinfunction "D_2") (pintype "input"))
    )
    (net (code "177") (name "unconnected-(IC4A-PRE-Pad4)") (class "Default")
      (node (ref "IC4") (pin "4") (pinfunction "PRE_4") (pintype "input"))
    )
    (net (code "178") (name "unconnected-(IC4A-Q-Pad5)") (class "Default")
      (node (ref "IC4") (pin "5") (pinfunction "Q_5") (pintype "output"))
    )
    (net (code "179") (name "unconnected-(IC4A-~{Q}-Pad6)") (class "Default")
      (node (ref "IC4") (pin "6") (pinfunction "~{Q}_6") (pintype "output"))
    )
    (net (code "180") (name "unconnected-(IC5B-~{Q}-Pad8)") (class "Default")
      (node (ref "IC5") (pin "8") (pinfunction "~{Q}_8") (pintype "output"))
    )
    (net (code "181") (name "unconnected-(IC6A-1A-Pad2)") (class "Default")
      (node (ref "IC6") (pin "2") (pinfunction "1A_2") (pintype "input"))
    )
    (net (code "182") (name "unconnected-(IC6A-1B-Pad3)") (class "Default")
      (node (ref "IC6") (pin "3") (pinfunction "1B_3") (pintype "input"))
    )
    (net (code "183") (name "unconnected-(IC6A-1Y-Pad4)") (class "Default")
      (node (ref "IC6") (pin "4") (pinfunction "1Y_4") (pintype "output"))
    )
    (net (code "184") (name "unconnected-(IC6A-3A-Pad11)") (class "Default")
      (node (ref "IC6") (pin "11") (pinfunction "3A_11") (pintype "input"))
    )
    (net (code "185") (name "unconnected-(IC6A-3B-Pad10)") (class "Default")
      (node (ref "IC6") (pin "10") (pinfunction "3B_10") (pintype "input"))
    )
    (net (code "186") (name "unconnected-(IC6A-3Y-Pad9)") (class "Default")
      (node (ref "IC6") (pin "9") (pinfunction "3Y_9") (pintype "output"))
    )
    (net (code "187") (name "unconnected-(IC9A-1A-Pad2)") (class "Default")
      (node (ref "IC9") (pin "2") (pinfunction "1A_2") (pintype "input"))
    )
    (net (code "188") (name "unconnected-(IC9A-1B-Pad3)") (class "Default")
      (node (ref "IC9") (pin "3") (pinfunction "1B_3") (pintype "input"))
    )
    (net (code "189") (name "unconnected-(IC9A-1Y-Pad4)") (class "Default")
      (node (ref "IC9") (pin "4") (pinfunction "1Y_4") (pintype "output"))
    )
    (net (code "190") (name "unconnected-(IC12-CHA_O-Pad11)") (class "Default")
      (node (ref "IC12") (pin "11") (pinfunction "CHA_O_11") (pintype "input"))
    )
    (net (code "191") (name "unconnected-(L1B-S1-PadS2)") (class "Default")
      (node (ref "L1") (pin "S2") (pinfunction "S1_S2") (pintype "passive"))
    )
    (net (code "192") (name "unconnected-(L1B-S2-PadS1)") (class "Default")
      (node (ref "L1") (pin "S1") (pinfunction "S2_S1") (pintype "passive"))
    )
    (net (code "193") (name "unconnected-(U$1AX-EDGE-Pad28B)") (class "Default")
      (node (ref "U$1") (pin "28B") (pinfunction "EDGE_28B") (pintype "bidirectional"))
    )
    (net (code "194") (name "unconnected-(U$1F-EDGE-Pad15A)") (class "Default")
      (node (ref "U$1") (pin "15A") (pinfunction "EDGE_15A") (pintype "bidirectional"))
    )
    (net (code "195") (name "unconnected-(U$1G-EDGE-Pad16A)") (class "Default")
      (node (ref "U$1") (pin "16A") (pinfunction "EDGE_16A") (pintype "bidirectional"))
    )
    (net (code "196") (name "unconnected-(U$1H-EDGE-Pad17A)") (class "Default")
      (node (ref "U$1") (pin "17A") (pinfunction "EDGE_17A") (pintype "bidirectional"))
    )
    (net (code "197") (name "unconnected-(U$1I-EDGE-Pad18A)") (class "Default")
      (node (ref "U$1") (pin "18A") (pinfunction "EDGE_18A") (pintype "bidirectional"))
    )
  )
)
